# microzed_breakout_v0_6_0b79851d.net
KiCad netlist of a schematic drawn in EAGLE
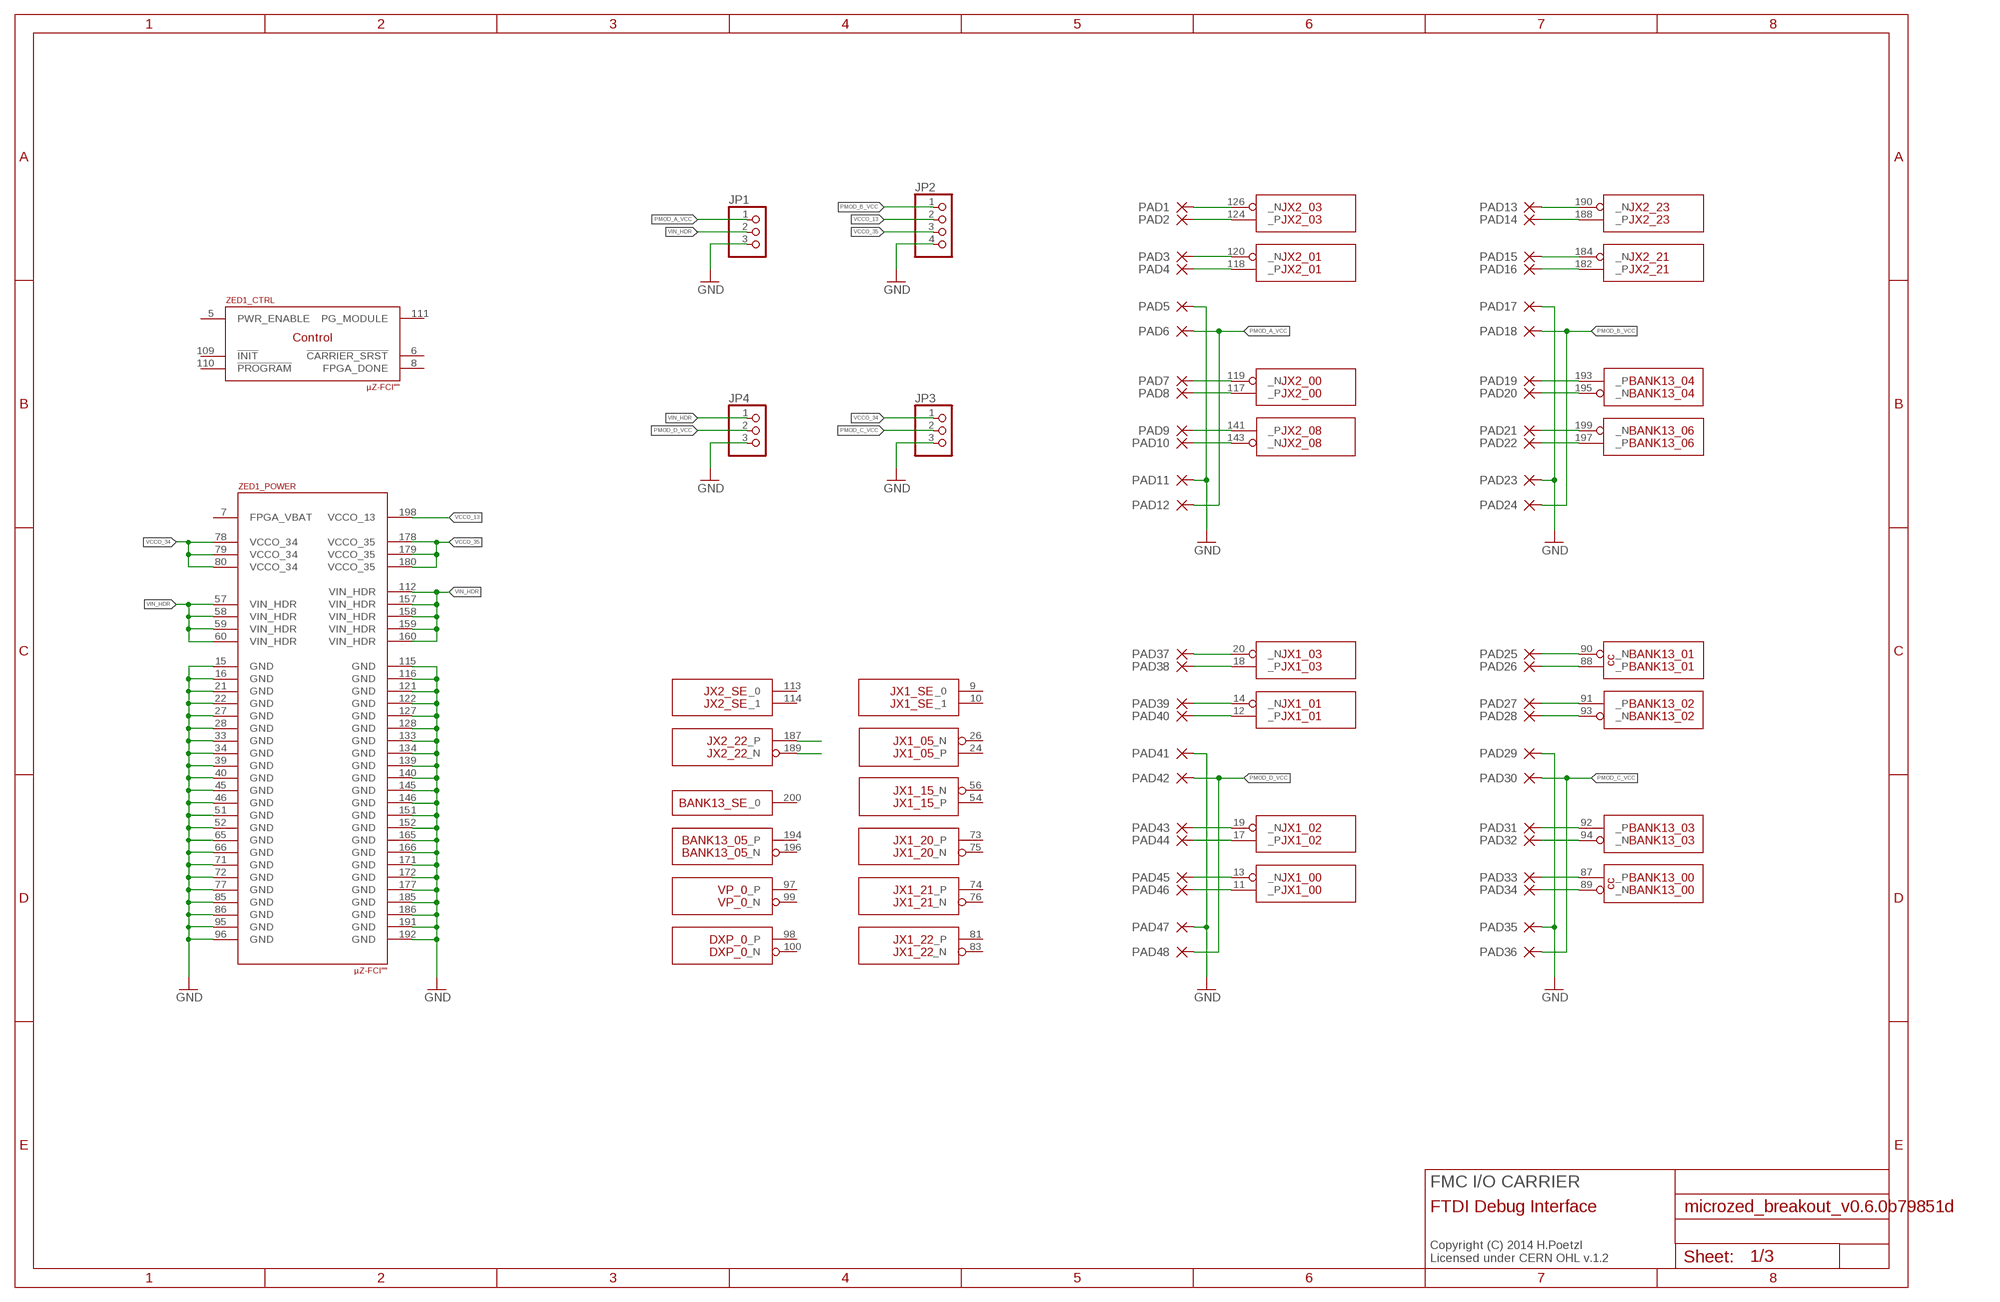
[diagram p0: schematic, sheet 1]
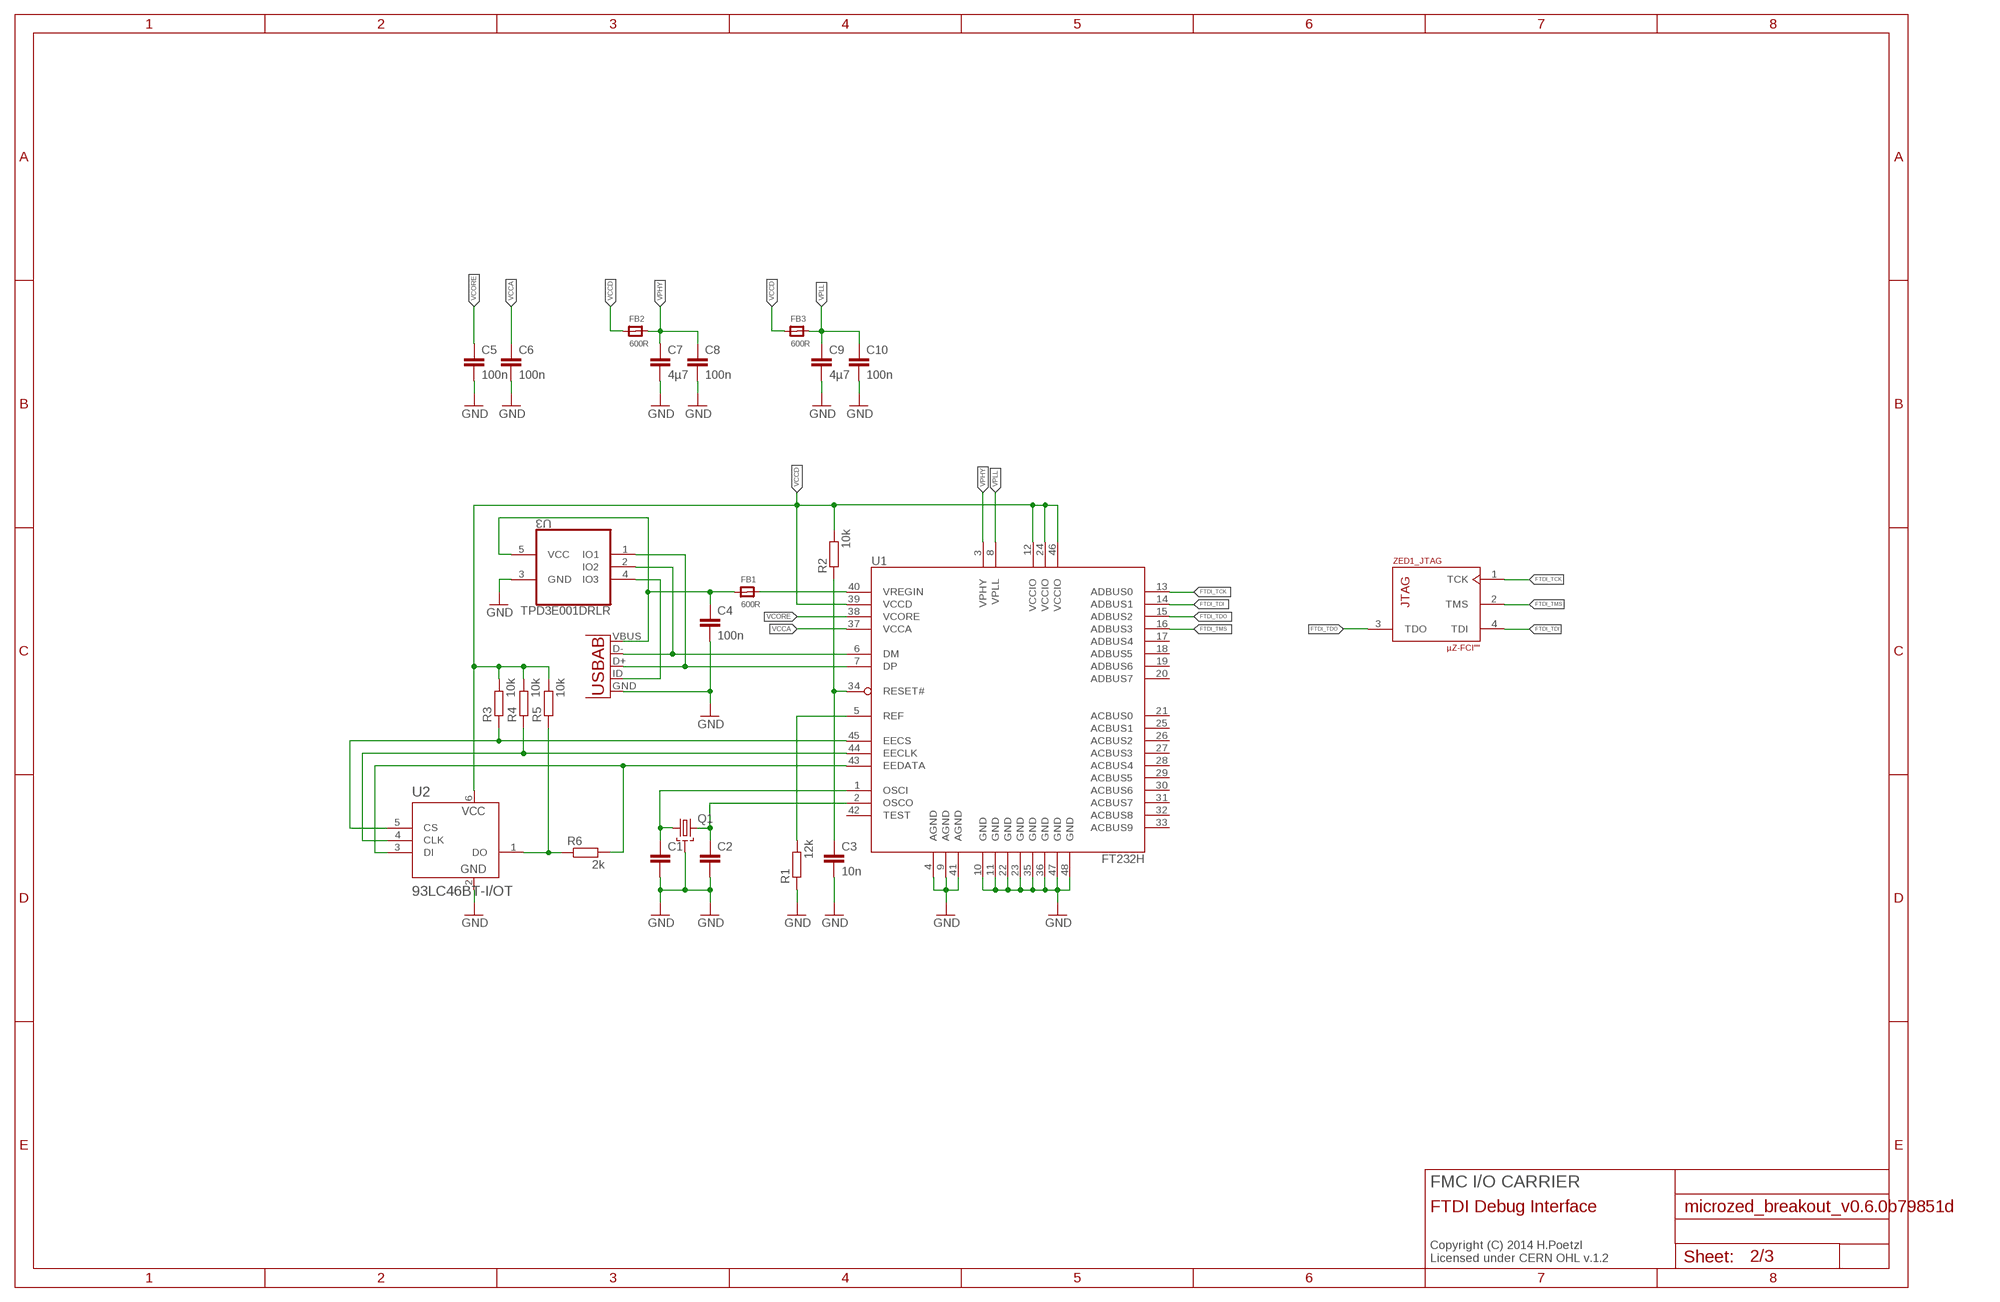
[diagram p1: schematic, sheet 2]
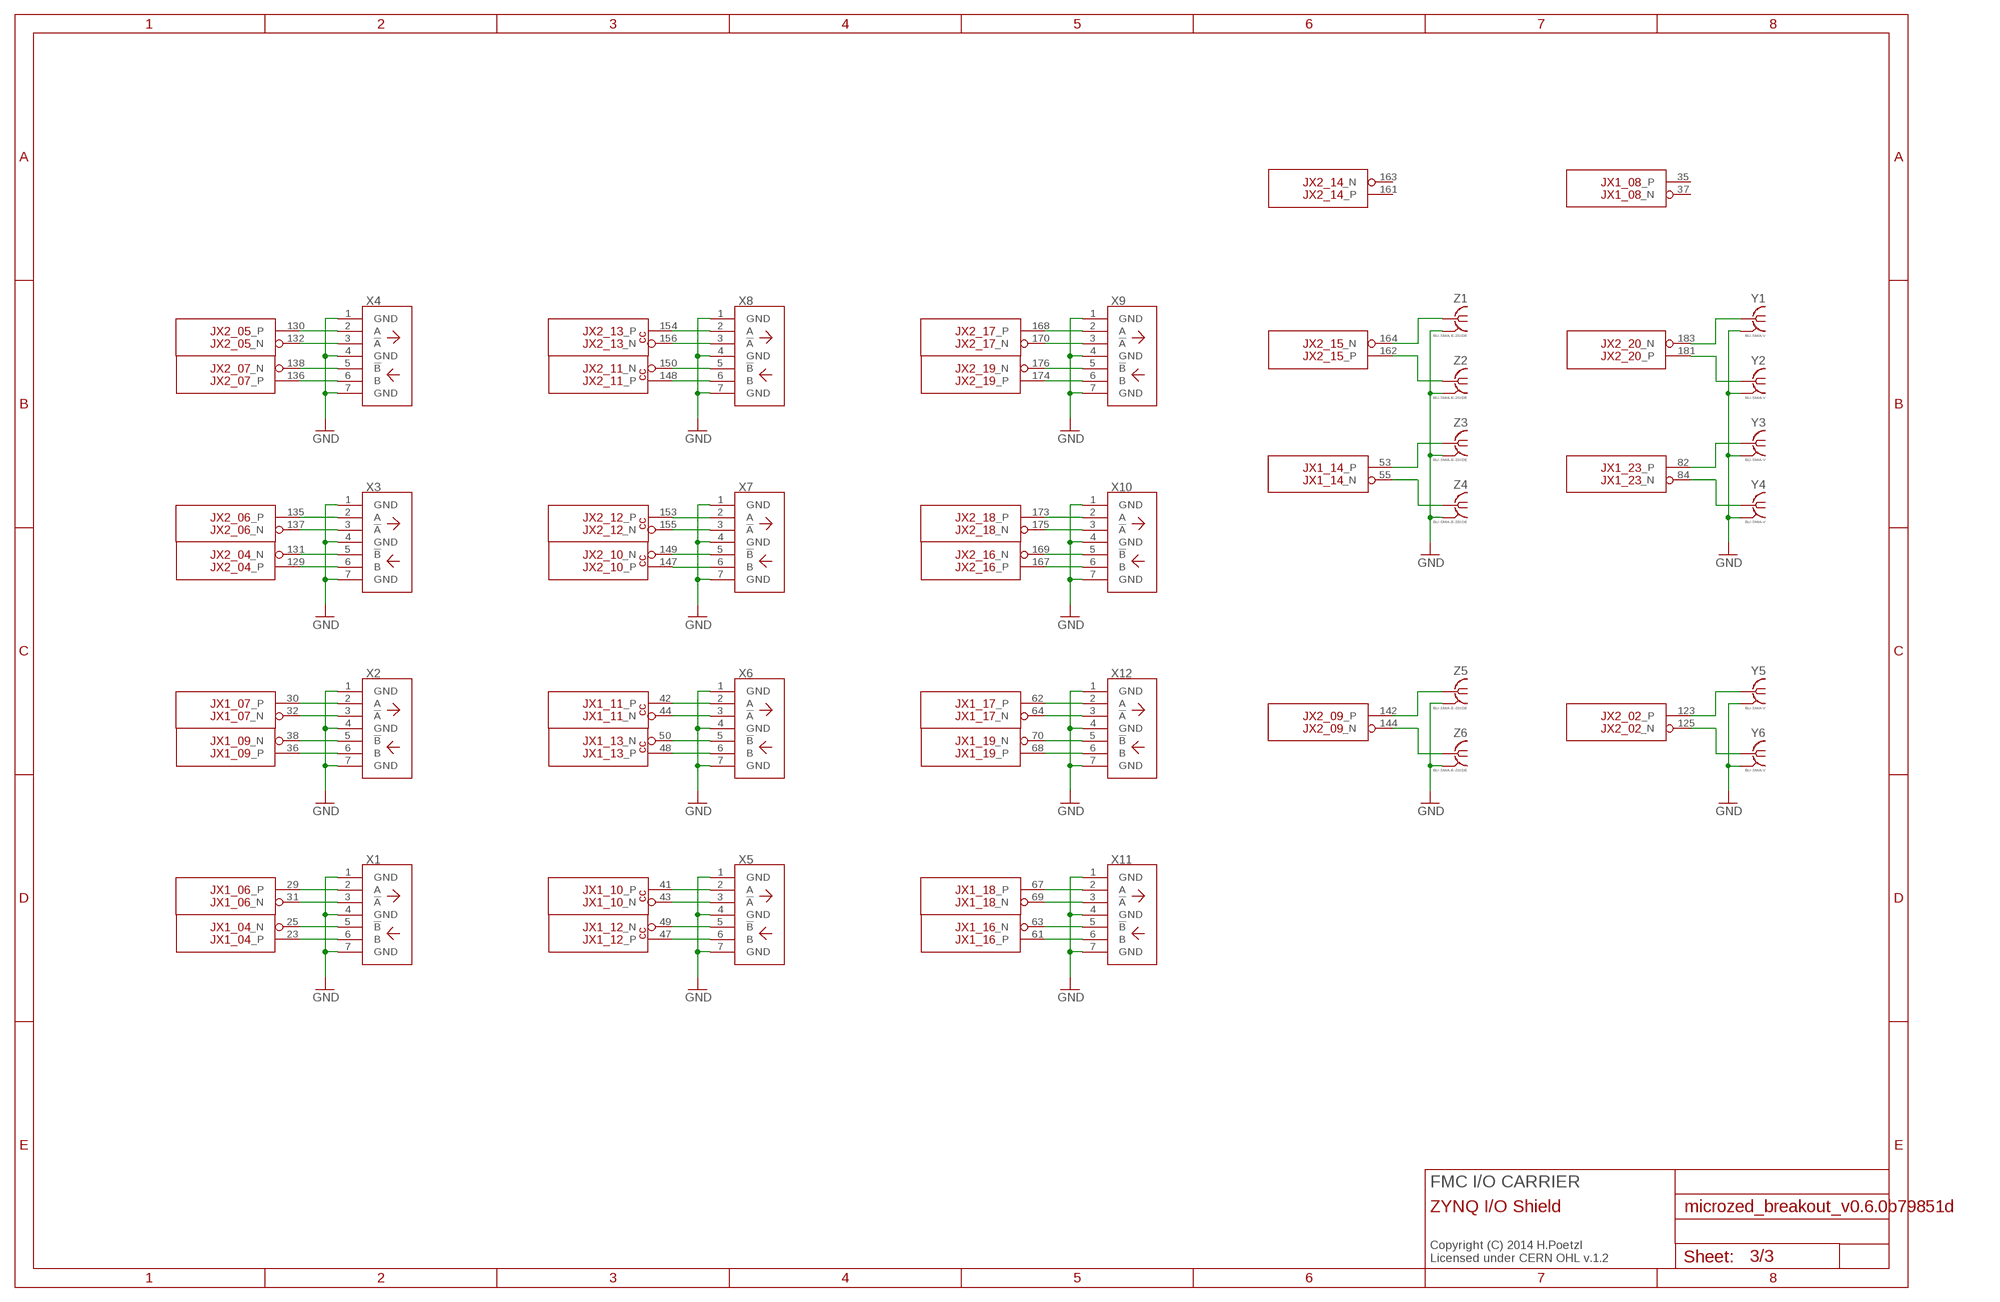
[diagram p2: schematic, sheet 3]

(export (version "E")
  (design (tool "Eeschema 10.0.6"))
  (components
    (comp (ref "C1")
      (value "C-EUC0402K")
      (footprint "eagle-import:C0402K")
      (libsource (lib "eagle-import") (part "C-EUC0402K"))
    )
    (comp (ref "C2")
      (value "C-EUC0402K")
      (footprint "eagle-import:C0402K")
      (libsource (lib "eagle-import") (part "C-EUC0402K"))
    )
    (comp (ref "C3")
      (value "10n")
      (footprint "eagle-import:C0402K")
      (libsource (lib "eagle-import") (part "C-EUC0402K"))
    )
    (comp (ref "C4")
      (value "100n")
      (footprint "eagle-import:C0402K")
      (libsource (lib "eagle-import") (part "C-EUC0402K"))
    )
    (comp (ref "C5")
      (value "100n")
      (footprint "eagle-import:C0402K")
      (libsource (lib "eagle-import") (part "C-EUC0402K"))
    )
    (comp (ref "C6")
      (value "100n")
      (footprint "eagle-import:C0402K")
      (libsource (lib "eagle-import") (part "C-EUC0402K"))
    )
    (comp (ref "C7")
      (value "4µ7")
      (footprint "eagle-import:C0402K")
      (libsource (lib "eagle-import") (part "C-EUC0402K"))
    )
    (comp (ref "C8")
      (value "100n")
      (footprint "eagle-import:C0402K")
      (libsource (lib "eagle-import") (part "C-EUC0402K"))
    )
    (comp (ref "C9")
      (value "4µ7")
      (footprint "eagle-import:C0402K")
      (libsource (lib "eagle-import") (part "C-EUC0402K"))
    )
    (comp (ref "C10")
      (value "100n")
      (footprint "eagle-import:C0402K")
      (libsource (lib "eagle-import") (part "C-EUC0402K"))
    )
    (comp (ref "FB1")
      (value "600R")
      (footprint "eagle-import:_0603MP")
      (libsource (lib "eagle-import") (part "FERRITE_0603MP"))
    )
    (comp (ref "FB2")
      (value "600R")
      (footprint "eagle-import:_0603MP")
      (libsource (lib "eagle-import") (part "FERRITE_0603MP"))
    )
    (comp (ref "FB3")
      (value "600R")
      (footprint "eagle-import:_0603MP")
      (libsource (lib "eagle-import") (part "FERRITE_0603MP"))
    )
    (comp (ref "Q1")
      (value "SMD-4P-2G-3.2X2.5")
      (footprint "eagle-import:ABM8G")
      (libsource (lib "eagle-import") (part "SMD-4P-2G-3.2X2.5"))
    )
    (comp (ref "R1")
      (value "12k")
      (footprint "eagle-import:R0402")
      (libsource (lib "eagle-import") (part "R-EU_R0402"))
    )
    (comp (ref "R2")
      (value "10k")
      (footprint "eagle-import:R0402")
      (libsource (lib "eagle-import") (part "R-EU_R0402"))
    )
    (comp (ref "R3")
      (value "10k")
      (footprint "eagle-import:R0402")
      (libsource (lib "eagle-import") (part "R-EU_R0402"))
    )
    (comp (ref "R4")
      (value "10k")
      (footprint "eagle-import:R0402")
      (libsource (lib "eagle-import") (part "R-EU_R0402"))
    )
    (comp (ref "R5")
      (value "10k")
      (footprint "eagle-import:R0402")
      (libsource (lib "eagle-import") (part "R-EU_R0402"))
    )
    (comp (ref "R6")
      (value "2k")
      (footprint "eagle-import:R0402")
      (libsource (lib "eagle-import") (part "R-EU_R0402"))
    )
    (comp (ref "U1")
      (value "FT232H")
      (footprint "eagle-import:LQFP48")
      (libsource (lib "eagle-import") (part "FT232H"))
    )
    (comp (ref "U2")
      (value "93LC46BT-I/OT")
      (footprint "eagle-import:SOT95P280X145-6N")
      (libsource (lib "eagle-import") (part "93LC46BT-I/OT"))
    )
    (comp (ref "U3")
      (value "TPD3E001DRLR")
      (footprint "eagle-import:SOT50P160X60-5N")
      (libsource (lib "eagle-import") (part "TPD3E001DRLR"))
    )
    (comp (ref "USB")
      (value "USB-AB")
      (footprint "eagle-import:USB-AB-MICRO-SMD")
      (libsource (lib "eagle-import") (part "USB-AB"))
    )
    (comp (ref "ZED1")
      (value "µZ-FCI\"\"")
      (footprint "eagle-import:µZ")
      (libsource (lib "eagle-import") (part "µZ-FCI{dblquote}{dblquote}"))
    )
    (comp (ref "X1")
      (value "SATA7-SMD-VERT")
      (footprint "eagle-import:SATA7-SMD-VERT")
      (libsource (lib "eagle-import") (part "SATA7-SMD-VERT"))
    )
    (comp (ref "X2")
      (value "SATA7-VERT")
      (footprint "eagle-import:SATA7-VERT")
      (libsource (lib "eagle-import") (part "SATA7-VERT"))
    )
    (comp (ref "X3")
      (value "SATA7-VERT")
      (footprint "eagle-import:SATA7-VERT")
      (libsource (lib "eagle-import") (part "SATA7-VERT"))
    )
    (comp (ref "X4")
      (value "SATA7-SMD-VERT")
      (footprint "eagle-import:SATA7-SMD-VERT")
      (libsource (lib "eagle-import") (part "SATA7-SMD-VERT"))
    )
    (comp (ref "X5")
      (value "SATA7-SMD-VERT")
      (footprint "eagle-import:SATA7-SMD-VERT")
      (libsource (lib "eagle-import") (part "SATA7-SMD-VERT"))
    )
    (comp (ref "X6")
      (value "SATA7-VERT")
      (footprint "eagle-import:SATA7-VERT")
      (libsource (lib "eagle-import") (part "SATA7-VERT"))
    )
    (comp (ref "X7")
      (value "SATA7-VERT")
      (footprint "eagle-import:SATA7-VERT")
      (libsource (lib "eagle-import") (part "SATA7-VERT"))
    )
    (comp (ref "X8")
      (value "SATA7-SMD-VERT")
      (footprint "eagle-import:SATA7-SMD-VERT")
      (libsource (lib "eagle-import") (part "SATA7-SMD-VERT"))
    )
    (comp (ref "X9")
      (value "SATA7-SMD-VERT")
      (footprint "eagle-import:SATA7-SMD-VERT")
      (libsource (lib "eagle-import") (part "SATA7-SMD-VERT"))
    )
    (comp (ref "X10")
      (value "SATA7-VERT")
      (footprint "eagle-import:SATA7-VERT")
      (libsource (lib "eagle-import") (part "SATA7-VERT"))
    )
    (comp (ref "X11")
      (value "SATA7-SMD-VERT")
      (footprint "eagle-import:SATA7-SMD-VERT")
      (libsource (lib "eagle-import") (part "SATA7-SMD-VERT"))
    )
    (comp (ref "X12")
      (value "SATA7-VERT")
      (footprint "eagle-import:SATA7-VERT")
      (libsource (lib "eagle-import") (part "SATA7-VERT"))
    )
    (comp (ref "Y1")
      (value "BU-SMA-V")
      (footprint "eagle-import:BU-SMA-V")
      (libsource (lib "eagle-import") (part "BU-SMA-V"))
    )
    (comp (ref "Y2")
      (value "BU-SMA-V")
      (footprint "eagle-import:BU-SMA-V")
      (libsource (lib "eagle-import") (part "BU-SMA-V"))
    )
    (comp (ref "Y3")
      (value "BU-SMA-V")
      (footprint "eagle-import:BU-SMA-V")
      (libsource (lib "eagle-import") (part "BU-SMA-V"))
    )
    (comp (ref "Y4")
      (value "BU-SMA-V")
      (footprint "eagle-import:BU-SMA-V")
      (libsource (lib "eagle-import") (part "BU-SMA-V"))
    )
    (comp (ref "Y5")
      (value "BU-SMA-V")
      (footprint "eagle-import:BU-SMA-V")
      (libsource (lib "eagle-import") (part "BU-SMA-V"))
    )
    (comp (ref "Y6")
      (value "BU-SMA-V")
      (footprint "eagle-import:BU-SMA-V")
      (libsource (lib "eagle-import") (part "BU-SMA-V"))
    )
    (comp (ref "Z1")
      (value "BU-SMA-E-2SIDE")
      (footprint "eagle-import:SMA_EDGE_2SIDE")
      (libsource (lib "eagle-import") (part "BU-SMA-E-2SIDE"))
    )
    (comp (ref "Z2")
      (value "BU-SMA-E-2SIDE")
      (footprint "eagle-import:SMA_EDGE_2SIDE")
      (libsource (lib "eagle-import") (part "BU-SMA-E-2SIDE"))
    )
    (comp (ref "Z3")
      (value "BU-SMA-E-2SIDE")
      (footprint "eagle-import:SMA_EDGE_2SIDE")
      (libsource (lib "eagle-import") (part "BU-SMA-E-2SIDE"))
    )
    (comp (ref "Z4")
      (value "BU-SMA-E-2SIDE")
      (footprint "eagle-import:SMA_EDGE_2SIDE")
      (libsource (lib "eagle-import") (part "BU-SMA-E-2SIDE"))
    )
    (comp (ref "Z5")
      (value "BU-SMA-E-2SIDE")
      (footprint "eagle-import:SMA_EDGE_2SIDE")
      (libsource (lib "eagle-import") (part "BU-SMA-E-2SIDE"))
    )
    (comp (ref "Z6")
      (value "BU-SMA-E-2SIDE")
      (footprint "eagle-import:SMA_EDGE_2SIDE")
      (libsource (lib "eagle-import") (part "BU-SMA-E-2SIDE"))
    )
    (comp (ref "JP1")
      (value "PINHD-1X03_2.54")
      (footprint "eagle-import:1X03")
      (libsource (lib "eagle-import") (part "PINHD-1X03_2.54"))
    )
    (comp (ref "JP2")
      (value "PINHD-1X04_2.54")
      (footprint "eagle-import:1X04")
      (libsource (lib "eagle-import") (part "PINHD-1X04_2.54"))
    )
    (comp (ref "JP3")
      (value "PINHD-1X03_2.54")
      (footprint "eagle-import:1X03")
      (libsource (lib "eagle-import") (part "PINHD-1X03_2.54"))
    )
    (comp (ref "JP4")
      (value "PINHD-1X03_2.54")
      (footprint "eagle-import:1X03")
      (libsource (lib "eagle-import") (part "PINHD-1X03_2.54"))
    )
    (comp (ref "PAD1")
      (value "SMD-PAD1.6X3.8MM-U")
      (footprint "eagle-import:1.6X3.8U-MM")
      (libsource (lib "eagle-import") (part "SMD-PAD1.6X3.8MM-U"))
    )
    (comp (ref "PAD2")
      (value "SMD-PAD1.6X3.8MM-U")
      (footprint "eagle-import:1.6X3.8U-MM")
      (libsource (lib "eagle-import") (part "SMD-PAD1.6X3.8MM-U"))
    )
    (comp (ref "PAD3")
      (value "SMD-PAD1.6X3.8MM-U")
      (footprint "eagle-import:1.6X3.8U-MM")
      (libsource (lib "eagle-import") (part "SMD-PAD1.6X3.8MM-U"))
    )
    (comp (ref "PAD4")
      (value "SMD-PAD1.6X3.8MM-U")
      (footprint "eagle-import:1.6X3.8U-MM")
      (libsource (lib "eagle-import") (part "SMD-PAD1.6X3.8MM-U"))
    )
    (comp (ref "PAD5")
      (value "SMD-PAD1.6X3.8MM-U")
      (footprint "eagle-import:1.6X3.8U-MM")
      (libsource (lib "eagle-import") (part "SMD-PAD1.6X3.8MM-U"))
    )
    (comp (ref "PAD6")
      (value "SMD-PAD1.6X3.8MM-U")
      (footprint "eagle-import:1.6X3.8U-MM")
      (libsource (lib "eagle-import") (part "SMD-PAD1.6X3.8MM-U"))
    )
    (comp (ref "PAD7")
      (value "SMD-PAD1.6X3.8MM-U")
      (footprint "eagle-import:1.6X3.8U-MM")
      (libsource (lib "eagle-import") (part "SMD-PAD1.6X3.8MM-U"))
    )
    (comp (ref "PAD8")
      (value "SMD-PAD1.6X3.8MM-U")
      (footprint "eagle-import:1.6X3.8U-MM")
      (libsource (lib "eagle-import") (part "SMD-PAD1.6X3.8MM-U"))
    )
    (comp (ref "PAD9")
      (value "SMD-PAD1.6X3.8MM-U")
      (footprint "eagle-import:1.6X3.8U-MM")
      (libsource (lib "eagle-import") (part "SMD-PAD1.6X3.8MM-U"))
    )
    (comp (ref "PAD10")
      (value "SMD-PAD1.6X3.8MM-U")
      (footprint "eagle-import:1.6X3.8U-MM")
      (libsource (lib "eagle-import") (part "SMD-PAD1.6X3.8MM-U"))
    )
    (comp (ref "PAD11")
      (value "SMD-PAD1.6X3.8MM-U")
      (footprint "eagle-import:1.6X3.8U-MM")
      (libsource (lib "eagle-import") (part "SMD-PAD1.6X3.8MM-U"))
    )
    (comp (ref "PAD12")
      (value "SMD-PAD1.6X3.8MM-U")
      (footprint "eagle-import:1.6X3.8U-MM")
      (libsource (lib "eagle-import") (part "SMD-PAD1.6X3.8MM-U"))
    )
    (comp (ref "PAD13")
      (value "SMD-PAD1.6X3.8MM-U")
      (footprint "eagle-import:1.6X3.8U-MM")
      (libsource (lib "eagle-import") (part "SMD-PAD1.6X3.8MM-U"))
    )
    (comp (ref "PAD14")
      (value "SMD-PAD1.6X3.8MM-U")
      (footprint "eagle-import:1.6X3.8U-MM")
      (libsource (lib "eagle-import") (part "SMD-PAD1.6X3.8MM-U"))
    )
    (comp (ref "PAD15")
      (value "SMD-PAD1.6X3.8MM-U")
      (footprint "eagle-import:1.6X3.8U-MM")
      (libsource (lib "eagle-import") (part "SMD-PAD1.6X3.8MM-U"))
    )
    (comp (ref "PAD16")
      (value "SMD-PAD1.6X3.8MM-U")
      (footprint "eagle-import:1.6X3.8U-MM")
      (libsource (lib "eagle-import") (part "SMD-PAD1.6X3.8MM-U"))
    )
    (comp (ref "PAD17")
      (value "SMD-PAD1.6X3.8MM-U")
      (footprint "eagle-import:1.6X3.8U-MM")
      (libsource (lib "eagle-import") (part "SMD-PAD1.6X3.8MM-U"))
    )
    (comp (ref "PAD18")
      (value "SMD-PAD1.6X3.8MM-U")
      (footprint "eagle-import:1.6X3.8U-MM")
      (libsource (lib "eagle-import") (part "SMD-PAD1.6X3.8MM-U"))
    )
    (comp (ref "PAD19")
      (value "SMD-PAD1.6X3.8MM-U")
      (footprint "eagle-import:1.6X3.8U-MM")
      (libsource (lib "eagle-import") (part "SMD-PAD1.6X3.8MM-U"))
    )
    (comp (ref "PAD20")
      (value "SMD-PAD1.6X3.8MM-U")
      (footprint "eagle-import:1.6X3.8U-MM")
      (libsource (lib "eagle-import") (part "SMD-PAD1.6X3.8MM-U"))
    )
    (comp (ref "PAD21")
      (value "SMD-PAD1.6X3.8MM-U")
      (footprint "eagle-import:1.6X3.8U-MM")
      (libsource (lib "eagle-import") (part "SMD-PAD1.6X3.8MM-U"))
    )
    (comp (ref "PAD22")
      (value "SMD-PAD1.6X3.8MM-U")
      (footprint "eagle-import:1.6X3.8U-MM")
      (libsource (lib "eagle-import") (part "SMD-PAD1.6X3.8MM-U"))
    )
    (comp (ref "PAD23")
      (value "SMD-PAD1.6X3.8MM-U")
      (footprint "eagle-import:1.6X3.8U-MM")
      (libsource (lib "eagle-import") (part "SMD-PAD1.6X3.8MM-U"))
    )
    (comp (ref "PAD24")
      (value "SMD-PAD1.6X3.8MM-U")
      (footprint "eagle-import:1.6X3.8U-MM")
      (libsource (lib "eagle-import") (part "SMD-PAD1.6X3.8MM-U"))
    )
    (comp (ref "PAD25")
      (value "SMD-PAD1.6X3.8MM-U")
      (footprint "eagle-import:1.6X3.8U-MM")
      (libsource (lib "eagle-import") (part "SMD-PAD1.6X3.8MM-U"))
    )
    (comp (ref "PAD26")
      (value "SMD-PAD1.6X3.8MM-U")
      (footprint "eagle-import:1.6X3.8U-MM")
      (libsource (lib "eagle-import") (part "SMD-PAD1.6X3.8MM-U"))
    )
    (comp (ref "PAD27")
      (value "SMD-PAD1.6X3.8MM-U")
      (footprint "eagle-import:1.6X3.8U-MM")
      (libsource (lib "eagle-import") (part "SMD-PAD1.6X3.8MM-U"))
    )
    (comp (ref "PAD28")
      (value "SMD-PAD1.6X3.8MM-U")
      (footprint "eagle-import:1.6X3.8U-MM")
      (libsource (lib "eagle-import") (part "SMD-PAD1.6X3.8MM-U"))
    )
    (comp (ref "PAD29")
      (value "SMD-PAD1.6X3.8MM-U")
      (footprint "eagle-import:1.6X3.8U-MM")
      (libsource (lib "eagle-import") (part "SMD-PAD1.6X3.8MM-U"))
    )
    (comp (ref "PAD30")
      (value "SMD-PAD1.6X3.8MM-U")
      (footprint "eagle-import:1.6X3.8U-MM")
      (libsource (lib "eagle-import") (part "SMD-PAD1.6X3.8MM-U"))
    )
    (comp (ref "PAD31")
      (value "SMD-PAD1.6X3.8MM-U")
      (footprint "eagle-import:1.6X3.8U-MM")
      (libsource (lib "eagle-import") (part "SMD-PAD1.6X3.8MM-U"))
    )
    (comp (ref "PAD32")
      (value "SMD-PAD1.6X3.8MM-U")
      (footprint "eagle-import:1.6X3.8U-MM")
      (libsource (lib "eagle-import") (part "SMD-PAD1.6X3.8MM-U"))
    )
    (comp (ref "PAD33")
      (value "SMD-PAD1.6X3.8MM-U")
      (footprint "eagle-import:1.6X3.8U-MM")
      (libsource (lib "eagle-import") (part "SMD-PAD1.6X3.8MM-U"))
    )
    (comp (ref "PAD34")
      (value "SMD-PAD1.6X3.8MM-U")
      (footprint "eagle-import:1.6X3.8U-MM")
      (libsource (lib "eagle-import") (part "SMD-PAD1.6X3.8MM-U"))
    )
    (comp (ref "PAD35")
      (value "SMD-PAD1.6X3.8MM-U")
      (footprint "eagle-import:1.6X3.8U-MM")
      (libsource (lib "eagle-import") (part "SMD-PAD1.6X3.8MM-U"))
    )
    (comp (ref "PAD36")
      (value "SMD-PAD1.6X3.8MM-U")
      (footprint "eagle-import:1.6X3.8U-MM")
      (libsource (lib "eagle-import") (part "SMD-PAD1.6X3.8MM-U"))
    )
    (comp (ref "PAD37")
      (value "SMD-PAD1.6X3.8MM-U")
      (footprint "eagle-import:1.6X3.8U-MM")
      (libsource (lib "eagle-import") (part "SMD-PAD1.6X3.8MM-U"))
    )
    (comp (ref "PAD38")
      (value "SMD-PAD1.6X3.8MM-U")
      (footprint "eagle-import:1.6X3.8U-MM")
      (libsource (lib "eagle-import") (part "SMD-PAD1.6X3.8MM-U"))
    )
    (comp (ref "PAD39")
      (value "SMD-PAD1.6X3.8MM-U")
      (footprint "eagle-import:1.6X3.8U-MM")
      (libsource (lib "eagle-import") (part "SMD-PAD1.6X3.8MM-U"))
    )
    (comp (ref "PAD40")
      (value "SMD-PAD1.6X3.8MM-U")
      (footprint "eagle-import:1.6X3.8U-MM")
      (libsource (lib "eagle-import") (part "SMD-PAD1.6X3.8MM-U"))
    )
    (comp (ref "PAD41")
      (value "SMD-PAD1.6X3.8MM-U")
      (footprint "eagle-import:1.6X3.8U-MM")
      (libsource (lib "eagle-import") (part "SMD-PAD1.6X3.8MM-U"))
    )
    (comp (ref "PAD42")
      (value "SMD-PAD1.6X3.8MM-U")
      (footprint "eagle-import:1.6X3.8U-MM")
      (libsource (lib "eagle-import") (part "SMD-PAD1.6X3.8MM-U"))
    )
    (comp (ref "PAD43")
      (value "SMD-PAD1.6X3.8MM-U")
      (footprint "eagle-import:1.6X3.8U-MM")
      (libsource (lib "eagle-import") (part "SMD-PAD1.6X3.8MM-U"))
    )
    (comp (ref "PAD44")
      (value "SMD-PAD1.6X3.8MM-U")
      (footprint "eagle-import:1.6X3.8U-MM")
      (libsource (lib "eagle-import") (part "SMD-PAD1.6X3.8MM-U"))
    )
    (comp (ref "PAD45")
      (value "SMD-PAD1.6X3.8MM-U")
      (footprint "eagle-import:1.6X3.8U-MM")
      (libsource (lib "eagle-import") (part "SMD-PAD1.6X3.8MM-U"))
    )
    (comp (ref "PAD46")
      (value "SMD-PAD1.6X3.8MM-U")
      (footprint "eagle-import:1.6X3.8U-MM")
      (libsource (lib "eagle-import") (part "SMD-PAD1.6X3.8MM-U"))
    )
    (comp (ref "PAD47")
      (value "SMD-PAD1.6X3.8MM-U")
      (footprint "eagle-import:1.6X3.8U-MM")
      (libsource (lib "eagle-import") (part "SMD-PAD1.6X3.8MM-U"))
    )
    (comp (ref "PAD48")
      (value "SMD-PAD1.6X3.8MM-U")
      (footprint "eagle-import:1.6X3.8U-MM")
      (libsource (lib "eagle-import") (part "SMD-PAD1.6X3.8MM-U"))
    )
  )
  (nets
    (net (code "1") (name "FPGA_VBAT") (class "Default")
      (node (ref "ZED1") (pin "7") (pinfunction "FPGA_VBAT_7") (pintype "power_in"))
    )
    (net (code "2") (name "FTDI_TCK") (class "Default")
      (node (ref "U1") (pin "13") (pinfunction "ADBUS0_13") (pintype "output"))
      (node (ref "ZED1") (pin "1") (pinfunction "TCK_1") (pintype "output"))
    )
    (net (code "3") (name "FTDI_TDI") (class "Default")
      (node (ref "U1") (pin "14") (pinfunction "ADBUS1_14") (pintype "input"))
      (node (ref "ZED1") (pin "4") (pinfunction "TDI_4") (pintype "output"))
    )
    (net (code "4") (name "FTDI_TDO") (class "Default")
      (node (ref "U1") (pin "15") (pinfunction "ADBUS2_15") (pintype "output"))
      (node (ref "ZED1") (pin "3") (pinfunction "TDO_3") (pintype "input"))
    )
    (net (code "5") (name "FTDI_TMS") (class "Default")
      (node (ref "U1") (pin "16") (pinfunction "ADBUS3_16") (pintype "input"))
      (node (ref "ZED1") (pin "2") (pinfunction "TMS_2") (pintype "output"))
    )
    (net (code "6") (name "GND") (class "Default")
      (node (ref "C1") (pin "2") (pinfunction "2_2") (pintype "passive"))
      (node (ref "C10") (pin "2") (pinfunction "2_2") (pintype "passive"))
      (node (ref "C2") (pin "2") (pinfunction "2_2") (pintype "passive"))
      (node (ref "C3") (pin "2") (pinfunction "2_2") (pintype "passive"))
      (node (ref "C4") (pin "2") (pinfunction "2_2") (pintype "passive"))
      (node (ref "C5") (pin "2") (pinfunction "2_2") (pintype "passive"))
      (node (ref "C6") (pin "2") (pinfunction "2_2") (pintype "passive"))
      (node (ref "C7") (pin "2") (pinfunction "2_2") (pintype "passive"))
      (node (ref "C8") (pin "2") (pinfunction "2_2") (pintype "passive"))
      (node (ref "C9") (pin "2") (pinfunction "2_2") (pintype "passive"))
      (node (ref "JP1") (pin "3") (pinfunction "3_3") (pintype "passive"))
      (node (ref "JP2") (pin "4") (pinfunction "4_4") (pintype "passive"))
      (node (ref "JP3") (pin "3") (pinfunction "3_3") (pintype "passive"))
      (node (ref "JP4") (pin "3") (pinfunction "3_3") (pintype "passive"))
      (node (ref "PAD11") (pin "1") (pinfunction "P_1") (pintype "passive"))
      (node (ref "PAD17") (pin "1") (pinfunction "P_1") (pintype "passive"))
      (node (ref "PAD23") (pin "1") (pinfunction "P_1") (pintype "passive"))
      (node (ref "PAD29") (pin "1") (pinfunction "P_1") (pintype "passive"))
      (node (ref "PAD35") (pin "1") (pinfunction "P_1") (pintype "passive"))
      (node (ref "PAD41") (pin "1") (pinfunction "P_1") (pintype "passive"))
      (node (ref "PAD47") (pin "1") (pinfunction "P_1") (pintype "passive"))
      (node (ref "PAD5") (pin "1") (pinfunction "P_1") (pintype "passive"))
      (node (ref "Q1") (pin "2") (pinfunction "GND_2") (pintype "power_in"))
      (node (ref "Q1") (pin "4") (pinfunction "GND_4") (pintype "power_in"))
      (node (ref "R1") (pin "1") (pinfunction "1_1") (pintype "passive"))
      (node (ref "U1") (pin "10") (pinfunction "GND_10") (pintype "power_in"))
      (node (ref "U1") (pin "11") (pinfunction "GND_11") (pintype "power_in"))
      (node (ref "U1") (pin "22") (pinfunction "GND_22") (pintype "power_in"))
      (node (ref "U1") (pin "23") (pinfunction "GND_23") (pintype "power_in"))
      (node (ref "U1") (pin "35") (pinfunction "GND_35") (pintype "power_in"))
      (node (ref "U1") (pin "36") (pinfunction "GND_36") (pintype "power_in"))
      (node (ref "U1") (pin "4") (pinfunction "AGND_4") (pintype "power_in"))
      (node (ref "U1") (pin "41") (pinfunction "AGND_41") (pintype "power_in"))
      (node (ref "U1") (pin "47") (pinfunction "GND_47") (pintype "power_in"))
      (node (ref "U1") (pin "48") (pinfunction "GND_48") (pintype "power_in"))
      (node (ref "U1") (pin "9") (pinfunction "AGND_9") (pintype "power_in"))
      (node (ref "U2") (pin "2") (pinfunction "VSS_2") (pintype "power_in"))
      (node (ref "U3") (pin "3") (pinfunction "GND_3") (pintype "passive"))
      (node (ref "USB") (pin "GND") (pinfunction "GND_GND") (pintype "bidirectional"))
      (node (ref "X1") (pin "1") (pinfunction "GND_1") (pintype "passive"))
      (node (ref "X1") (pin "4") (pinfunction "GND_4") (pintype "passive"))
      (node (ref "X1") (pin "7") (pinfunction "GND_7") (pintype "passive"))
      (node (ref "X10") (pin "1") (pinfunction "GND_1") (pintype "passive"))
      (node (ref "X10") (pin "4") (pinfunction "GND_4") (pintype "passive"))
      (node (ref "X10") (pin "7") (pinfunction "GND_7") (pintype "passive"))
      (node (ref "X11") (pin "1") (pinfunction "GND_1") (pintype "passive"))
      (node (ref "X11") (pin "4") (pinfunction "GND_4") (pintype "passive"))
      (node (ref "X11") (pin "7") (pinfunction "GND_7") (pintype "passive"))
      (node (ref "X12") (pin "1") (pinfunction "GND_1") (pintype "passive"))
      (node (ref "X12") (pin "4") (pinfunction "GND_4") (pintype "passive"))
      (node (ref "X12") (pin "7") (pinfunction "GND_7") (pintype "passive"))
      (node (ref "X2") (pin "1") (pinfunction "GND_1") (pintype "passive"))
      (node (ref "X2") (pin "4") (pinfunction "GND_4") (pintype "passive"))
      (node (ref "X2") (pin "7") (pinfunction "GND_7") (pintype "passive"))
      (node (ref "X3") (pin "1") (pinfunction "GND_1") (pintype "passive"))
      (node (ref "X3") (pin "4") (pinfunction "GND_4") (pintype "passive"))
      (node (ref "X3") (pin "7") (pinfunction "GND_7") (pintype "passive"))
      (node (ref "X4") (pin "1") (pinfunction "GND_1") (pintype "passive"))
      (node (ref "X4") (pin "4") (pinfunction "GND_4") (pintype "passive"))
      (node (ref "X4") (pin "7") (pinfunction "GND_7") (pintype "passive"))
      (node (ref "X5") (pin "1") (pinfunction "GND_1") (pintype "passive"))
      (node (ref "X5") (pin "4") (pinfunction "GND_4") (pintype "passive"))
      (node (ref "X5") (pin "7") (pinfunction "GND_7") (pintype "passive"))
      (node (ref "X6") (pin "1") (pinfunction "GND_1") (pintype "passive"))
      (node (ref "X6") (pin "4") (pinfunction "GND_4") (pintype "passive"))
      (node (ref "X6") (pin "7") (pinfunction "GND_7") (pintype "passive"))
      (node (ref "X7") (pin "1") (pinfunction "GND_1") (pintype "passive"))
      (node (ref "X7") (pin "4") (pinfunction "GND_4") (pintype "passive"))
      (node (ref "X7") (pin "7") (pinfunction "GND_7") (pintype "passive"))
      (node (ref "X8") (pin "1") (pinfunction "GND_1") (pintype "passive"))
      (node (ref "X8") (pin "4") (pinfunction "GND_4") (pintype "passive"))
      (node (ref "X8") (pin "7") (pinfunction "GND_7") (pintype "passive"))
      (node (ref "X9") (pin "1") (pinfunction "GND_1") (pintype "passive"))
      (node (ref "X9") (pin "4") (pinfunction "GND_4") (pintype "passive"))
      (node (ref "X9") (pin "7") (pinfunction "GND_7") (pintype "passive"))
      (node (ref "Y1") (pin "2") (pinfunction "2_2") (pintype "passive"))
      (node (ref "Y1") (pin "3") (pinfunction "2_3") (pintype "passive"))
      (node (ref "Y1") (pin "4") (pinfunction "2_4") (pintype "passive"))
      (node (ref "Y1") (pin "5") (pinfunction "2_5") (pintype "passive"))
      (node (ref "Y2") (pin "2") (pinfunction "2_2") (pintype "passive"))
      (node (ref "Y2") (pin "3") (pinfunction "2_3") (pintype "passive"))
      (node (ref "Y2") (pin "4") (pinfunction "2_4") (pintype "passive"))
      (node (ref "Y2") (pin "5") (pinfunction "2_5") (pintype "passive"))
      (node (ref "Y3") (pin "2") (pinfunction "2_2") (pintype "passive"))
      (node (ref "Y3") (pin "3") (pinfunction "2_3") (pintype "passive"))
      (node (ref "Y3") (pin "4") (pinfunction "2_4") (pintype "passive"))
      (node (ref "Y3") (pin "5") (pinfunction "2_5") (pintype "passive"))
      (node (ref "Y4") (pin "2") (pinfunction "2_2") (pintype "passive"))
      (node (ref "Y4") (pin "3") (pinfunction "2_3") (pintype "passive"))
      (node (ref "Y4") (pin "4") (pinfunction "2_4") (pintype "passive"))
      (node (ref "Y4") (pin "5") (pinfunction "2_5") (pintype "passive"))
      (node (ref "Y5") (pin "2") (pinfunction "2_2") (pintype "passive"))
      (node (ref "Y5") (pin "3") (pinfunction "2_3") (pintype "passive"))
      (node (ref "Y5") (pin "4") (pinfunction "2_4") (pintype "passive"))
      (node (ref "Y5") (pin "5") (pinfunction "2_5") (pintype "passive"))
      (node (ref "Y6") (pin "2") (pinfunction "2_2") (pintype "passive"))
      (node (ref "Y6") (pin "3") (pinfunction "2_3") (pintype "passive"))
      (node (ref "Y6") (pin "4") (pinfunction "2_4") (pintype "passive"))
      (node (ref "Y6") (pin "5") (pinfunction "2_5") (pintype "passive"))
      (node (ref "Z1") (pin "2@1") (pinfunction "2_2@1") (pintype "passive"))
      (node (ref "Z1") (pin "2@2") (pinfunction "2_2@2") (pintype "passive"))
      (node (ref "Z1") (pin "2@3") (pinfunction "2_2@3") (pintype "passive"))
      (node (ref "Z1") (pin "2@4") (pinfunction "2_2@4") (pintype "passive"))
      (node (ref "Z2") (pin "2@1") (pinfunction "2_2@1") (pintype "passive"))
      (node (ref "Z2") (pin "2@2") (pinfunction "2_2@2") (pintype "passive"))
      (node (ref "Z2") (pin "2@3") (pinfunction "2_2@3") (pintype "passive"))
      (node (ref "Z2") (pin "2@4") (pinfunction "2_2@4") (pintype "passive"))
      (node (ref "Z3") (pin "2@1") (pinfunction "2_2@1") (pintype "passive"))
      (node (ref "Z3") (pin "2@2") (pinfunction "2_2@2") (pintype "passive"))
      (node (ref "Z3") (pin "2@3") (pinfunction "2_2@3") (pintype "passive"))
      (node (ref "Z3") (pin "2@4") (pinfunction "2_2@4") (pintype "passive"))
      (node (ref "Z4") (pin "2@1") (pinfunction "2_2@1") (pintype "passive"))
      (node (ref "Z4") (pin "2@2") (pinfunction "2_2@2") (pintype "passive"))
      (node (ref "Z4") (pin "2@3") (pinfunction "2_2@3") (pintype "passive"))
      (node (ref "Z4") (pin "2@4") (pinfunction "2_2@4") (pintype "passive"))
      (node (ref "Z5") (pin "2@1") (pinfunction "2_2@1") (pintype "passive"))
      (node (ref "Z5") (pin "2@2") (pinfunction "2_2@2") (pintype "passive"))
      (node (ref "Z5") (pin "2@3") (pinfunction "2_2@3") (pintype "passive"))
      (node (ref "Z5") (pin "2@4") (pinfunction "2_2@4") (pintype "passive"))
      (node (ref "Z6") (pin "2@1") (pinfunction "2_2@1") (pintype "passive"))
      (node (ref "Z6") (pin "2@2") (pinfunction "2_2@2") (pintype "passive"))
      (node (ref "Z6") (pin "2@3") (pinfunction "2_2@3") (pintype "passive"))
      (node (ref "Z6") (pin "2@4") (pinfunction "2_2@4") (pintype "passive"))
      (node (ref "ZED1") (pin "115") (pinfunction "GND_115") (pintype "power_in"))
      (node (ref "ZED1") (pin "116") (pinfunction "GND_116") (pintype "power_in"))
      (node (ref "ZED1") (pin "121") (pinfunction "GND_121") (pintype "power_in"))
      (node (ref "ZED1") (pin "122") (pinfunction "GND_122") (pintype "power_in"))
      (node (ref "ZED1") (pin "127") (pinfunction "GND_127") (pintype "power_in"))
      (node (ref "ZED1") (pin "128") (pinfunction "GND_128") (pintype "power_in"))
      (node (ref "ZED1") (pin "133") (pinfunction "GND_133") (pintype "power_in"))
      (node (ref "ZED1") (pin "134") (pinfunction "GND_134") (pintype "power_in"))
      (node (ref "ZED1") (pin "139") (pinfunction "GND_139") (pintype "power_in"))
      (node (ref "ZED1") (pin "140") (pinfunction "GND_140") (pintype "power_in"))
      (node (ref "ZED1") (pin "145") (pinfunction "GND_145") (pintype "power_in"))
      (node (ref "ZED1") (pin "146") (pinfunction "GND_146") (pintype "power_in"))
      (node (ref "ZED1") (pin "15") (pinfunction "GND_15") (pintype "power_in"))
      (node (ref "ZED1") (pin "151") (pinfunction "GND_151") (pintype "power_in"))
      (node (ref "ZED1") (pin "152") (pinfunction "GND_152") (pintype "power_in"))
      (node (ref "ZED1") (pin "16") (pinfunction "GND_16") (pintype "power_in"))
      (node (ref "ZED1") (pin "165") (pinfunction "GND_165") (pintype "power_in"))
      (node (ref "ZED1") (pin "166") (pinfunction "GND_166") (pintype "power_in"))
      (node (ref "ZED1") (pin "171") (pinfunction "GND_171") (pintype "power_in"))
      (node (ref "ZED1") (pin "172") (pinfunction "GND_172") (pintype "power_in"))
      (node (ref "ZED1") (pin "177") (pinfunction "GND_177") (pintype "power_in"))
      (node (ref "ZED1") (pin "185") (pinfunction "GND_185") (pintype "power_in"))
      (node (ref "ZED1") (pin "186") (pinfunction "GND_186") (pintype "power_in"))
      (node (ref "ZED1") (pin "191") (pinfunction "GND_191") (pintype "power_in"))
      (node (ref "ZED1") (pin "192") (pinfunction "GND_192") (pintype "power_in"))
      (node (ref "ZED1") (pin "21") (pinfunction "GND_21") (pintype "power_in"))
      (node (ref "ZED1") (pin "22") (pinfunction "GND_22") (pintype "power_in"))
      (node (ref "ZED1") (pin "27") (pinfunction "GND_27") (pintype "power_in"))
      (node (ref "ZED1") (pin "28") (pinfunction "GND_28") (pintype "power_in"))
      (node (ref "ZED1") (pin "33") (pinfunction "GND_33") (pintype "power_in"))
      (node (ref "ZED1") (pin "34") (pinfunction "GND_34") (pintype "power_in"))
      (node (ref "ZED1") (pin "39") (pinfunction "GND_39") (pintype "power_in"))
      (node (ref "ZED1") (pin "40") (pinfunction "GND_40") (pintype "power_in"))
      (node (ref "ZED1") (pin "45") (pinfunction "GND_45") (pintype "power_in"))
      (node (ref "ZED1") (pin "46") (pinfunction "GND_46") (pintype "power_in"))
      (node (ref "ZED1") (pin "51") (pinfunction "GND_51") (pintype "power_in"))
      (node (ref "ZED1") (pin "52") (pinfunction "GND_52") (pintype "power_in"))
      (node (ref "ZED1") (pin "65") (pinfunction "GND_65") (pintype "power_in"))
      (node (ref "ZED1") (pin "66") (pinfunction "GND_66") (pintype "power_in"))
      (node (ref "ZED1") (pin "71") (pinfunction "GND_71") (pintype "power_in"))
      (node (ref "ZED1") (pin "72") (pinfunction "GND_72") (pintype "power_in"))
      (node (ref "ZED1") (pin "77") (pinfunction "GND_77") (pintype "power_in"))
      (node (ref "ZED1") (pin "85") (pinfunction "GND_85") (pintype "power_in"))
      (node (ref "ZED1") (pin "86") (pinfunction "GND_86") (pintype "power_in"))
      (node (ref "ZED1") (pin "95") (pinfunction "GND_95") (pintype "power_in"))
      (node (ref "ZED1") (pin "96") (pinfunction "GND_96") (pintype "power_in"))
    )
    (net (code "7") (name "Net-(FB1-P$1)") (class "Default")
      (node (ref "C4") (pin "1") (pinfunction "1_1") (pintype "passive"))
      (node (ref "FB1") (pin "1") (pinfunction "P$1_1") (pintype "passive"))
      (node (ref "U3") (pin "5") (pinfunction "VCC_5") (pintype "power_in"))
      (node (ref "USB") (pin "VBUS") (pinfunction "VBUS_VBUS") (pintype "bidirectional"))
    )
    (net (code "8") (name "Net-(FB1-P$2)") (class "Default")
      (node (ref "FB1") (pin "2") (pinfunction "P$2_2") (pintype "passive"))
      (node (ref "U1") (pin "40") (pinfunction "VREGIN_40") (pintype "power_in"))
    )
    (net (code "9") (name "Net-(PAD1-P)") (class "Default")
      (node (ref "PAD1") (pin "1") (pinfunction "P_1") (pintype "passive"))
      (node (ref "ZED1") (pin "126") (pinfunction "_N_126") (pintype "bidirectional"))
    )
    (net (code "10") (name "Net-(PAD2-P)") (class "Default")
      (node (ref "PAD2") (pin "1") (pinfunction "P_1") (pintype "passive"))
      (node (ref "ZED1") (pin "124") (pinfunction "_P_124") (pintype "bidirectional"))
    )
    (net (code "11") (name "Net-(PAD3-P)") (class "Default")
      (node (ref "PAD3") (pin "1") (pinfunction "P_1") (pintype "passive"))
      (node (ref "ZED1") (pin "120") (pinfunction "_N_120") (pintype "bidirectional"))
    )
    (net (code "12") (name "Net-(PAD4-P)") (class "Default")
      (node (ref "PAD4") (pin "1") (pinfunction "P_1") (pintype "passive"))
      (node (ref "ZED1") (pin "118") (pinfunction "_P_118") (pintype "bidirectional"))
    )
    (net (code "13") (name "Net-(PAD7-P)") (class "Default")
      (node (ref "PAD7") (pin "1") (pinfunction "P_1") (pintype "passive"))
      (node (ref "ZED1") (pin "119") (pinfunction "_N_119") (pintype "bidirectional"))
    )
    (net (code "14") (name "Net-(PAD8-P)") (class "Default")
      (node (ref "PAD8") (pin "1") (pinfunction "P_1") (pintype "passive"))
      (node (ref "ZED1") (pin "117") (pinfunction "_P_117") (pintype "bidirectional"))
    )
    (net (code "15") (name "Net-(PAD9-P)") (class "Default")
      (node (ref "PAD9") (pin "1") (pinfunction "P_1") (pintype "passive"))
      (node (ref "ZED1") (pin "141") (pinfunction "_P_141") (pintype "bidirectional"))
    )
    (net (code "16") (name "Net-(PAD10-P)") (class "Default")
      (node (ref "PAD10") (pin "1") (pinfunction "P_1") (pintype "passive"))
      (node (ref "ZED1") (pin "143") (pinfunction "_N_143") (pintype "bidirectional"))
    )
    (net (code "17") (name "Net-(PAD13-P)") (class "Default")
      (node (ref "PAD13") (pin "1") (pinfunction "P_1") (pintype "passive"))
      (node (ref "ZED1") (pin "190") (pinfunction "_N_190") (pintype "bidirectional"))
    )
    (net (code "18") (name "Net-(PAD14-P)") (class "Default")
      (node (ref "PAD14") (pin "1") (pinfunction "P_1") (pintype "passive"))
      (node (ref "ZED1") (pin "188") (pinfunction "_P_188") (pintype "bidirectional"))
    )
    (net (code "19") (name "Net-(PAD15-P)") (class "Default")
      (node (ref "PAD15") (pin "1") (pinfunction "P_1") (pintype "passive"))
      (node (ref "ZED1") (pin "184") (pinfunction "_N_184") (pintype "bidirectional"))
    )
    (net (code "20") (name "Net-(PAD16-P)") (class "Default")
      (node (ref "PAD16") (pin "1") (pinfunction "P_1") (pintype "passive"))
      (node (ref "ZED1") (pin "182") (pinfunction "_P_182") (pintype "bidirectional"))
    )
    (net (code "21") (name "Net-(PAD19-P)") (class "Default")
      (node (ref "PAD19") (pin "1") (pinfunction "P_1") (pintype "passive"))
      (node (ref "ZED1") (pin "193") (pinfunction "_P_193") (pintype "bidirectional"))
    )
    (net (code "22") (name "Net-(PAD20-P)") (class "Default")
      (node (ref "PAD20") (pin "1") (pinfunction "P_1") (pintype "passive"))
      (node (ref "ZED1") (pin "195") (pinfunction "_N_195") (pintype "bidirectional"))
    )
    (net (code "23") (name "Net-(PAD21-P)") (class "Default")
      (node (ref "PAD21") (pin "1") (pinfunction "P_1") (pintype "passive"))
      (node (ref "ZED1") (pin "199") (pinfunction "_N_199") (pintype "bidirectional"))
    )
    (net (code "24") (name "Net-(PAD22-P)") (class "Default")
      (node (ref "PAD22") (pin "1") (pinfunction "P_1") (pintype "passive"))
      (node (ref "ZED1") (pin "197") (pinfunction "_P_197") (pintype "bidirectional"))
    )
    (net (code "25") (name "Net-(PAD25-P)") (class "Default")
      (node (ref "PAD25") (pin "1") (pinfunction "P_1") (pintype "passive"))
      (node (ref "ZED1") (pin "90") (pinfunction "_N_90") (pintype "bidirectional"))
    )
    (net (code "26") (name "Net-(PAD26-P)") (class "Default")
      (node (ref "PAD26") (pin "1") (pinfunction "P_1") (pintype "passive"))
      (node (ref "ZED1") (pin "88") (pinfunction "_P_88") (pintype "bidirectional"))
    )
    (net (code "27") (name "Net-(PAD27-P)") (class "Default")
      (node (ref "PAD27") (pin "1") (pinfunction "P_1") (pintype "passive"))
      (node (ref "ZED1") (pin "91") (pinfunction "_P_91") (pintype "bidirectional"))
    )
    (net (code "28") (name "Net-(PAD28-P)") (class "Default")
      (node (ref "PAD28") (pin "1") (pinfunction "P_1") (pintype "passive"))
      (node (ref "ZED1") (pin "93") (pinfunction "_N_93") (pintype "bidirectional"))
    )
    (net (code "29") (name "Net-(PAD31-P)") (class "Default")
      (node (ref "PAD31") (pin "1") (pinfunction "P_1") (pintype "passive"))
      (node (ref "ZED1") (pin "92") (pinfunction "_P_92") (pintype "bidirectional"))
    )
    (net (code "30") (name "Net-(PAD32-P)") (class "Default")
      (node (ref "PAD32") (pin "1") (pinfunction "P_1") (pintype "passive"))
      (node (ref "ZED1") (pin "94") (pinfunction "_N_94") (pintype "bidirectional"))
    )
    (net (code "31") (name "Net-(PAD33-P)") (class "Default")
      (node (ref "PAD33") (pin "1") (pinfunction "P_1") (pintype "passive"))
      (node (ref "ZED1") (pin "87") (pinfunction "_P_87") (pintype "bidirectional"))
    )
    (net (code "32") (name "Net-(PAD34-P)") (class "Default")
      (node (ref "PAD34") (pin "1") (pinfunction "P_1") (pintype "passive"))
      (node (ref "ZED1") (pin "89") (pinfunction "_N_89") (pintype "bidirectional"))
    )
    (net (code "33") (name "Net-(PAD37-P)") (class "Default")
      (node (ref "PAD37") (pin "1") (pinfunction "P_1") (pintype "passive"))
      (node (ref "ZED1") (pin "20") (pinfunction "_N_20") (pintype "bidirectional"))
    )
    (net (code "34") (name "Net-(PAD38-P)") (class "Default")
      (node (ref "PAD38") (pin "1") (pinfunction "P_1") (pintype "passive"))
      (node (ref "ZED1") (pin "18") (pinfunction "_P_18") (pintype "bidirectional"))
    )
    (net (code "35") (name "Net-(PAD39-P)") (class "Default")
      (node (ref "PAD39") (pin "1") (pinfunction "P_1") (pintype "passive"))
      (node (ref "ZED1") (pin "14") (pinfunction "_N_14") (pintype "bidirectional"))
    )
    (net (code "36") (name "Net-(PAD40-P)") (class "Default")
      (node (ref "PAD40") (pin "1") (pinfunction "P_1") (pintype "passive"))
      (node (ref "ZED1") (pin "12") (pinfunction "_P_12") (pintype "bidirectional"))
    )
    (net (code "37") (name "Net-(PAD43-P)") (class "Default")
      (node (ref "PAD43") (pin "1") (pinfunction "P_1") (pintype "passive"))
      (node (ref "ZED1") (pin "19") (pinfunction "_N_19") (pintype "bidirectional"))
    )
    (net (code "38") (name "Net-(PAD44-P)") (class "Default")
      (node (ref "PAD44") (pin "1") (pinfunction "P_1") (pintype "passive"))
      (node (ref "ZED1") (pin "17") (pinfunction "_P_17") (pintype "bidirectional"))
    )
    (net (code "39") (name "Net-(PAD45-P)") (class "Default")
      (node (ref "PAD45") (pin "1") (pinfunction "P_1") (pintype "passive"))
      (node (ref "ZED1") (pin "13") (pinfunction "_N_13") (pintype "bidirectional"))
    )
    (net (code "40") (name "Net-(PAD46-P)") (class "Default")
      (node (ref "PAD46") (pin "1") (pinfunction "P_1") (pintype "passive"))
      (node (ref "ZED1") (pin "11") (pinfunction "_P_11") (pintype "bidirectional"))
    )
    (net (code "41") (name "Net-(Q1-2)") (class "Default")
      (node (ref "C2") (pin "1") (pinfunction "1_1") (pintype "passive"))
      (node (ref "Q1") (pin "3") (pinfunction "2_3") (pintype "passive"))
      (node (ref "U1") (pin "2") (pinfunction "OSCO_2") (pintype "output"))
    )
    (net (code "42") (name "Net-(U1-DM)") (class "Default")
      (node (ref "U1") (pin "6") (pinfunction "DM_6") (pintype "bidirectional"))
      (node (ref "U3") (pin "2") (pinfunction "IO2_2") (pintype "bidirectional"))
      (node (ref "USB") (pin "D-") (pinfunction "D-_D-") (pintype "bidirectional"))
    )
    (net (code "43") (name "Net-(U1-DP)") (class "Default")
      (node (ref "U1") (pin "7") (pinfunction "DP_7") (pintype "bidirectional"))
      (node (ref "U3") (pin "1") (pinfunction "IO1_1") (pintype "bidirectional"))
      (node (ref "USB") (pin "D+") (pinfunction "D+_D+") (pintype "bidirectional"))
    )
    (net (code "44") (name "Net-(U1-EECLK)") (class "Default")
      (node (ref "R4") (pin "1") (pinfunction "1_1") (pintype "passive"))
      (node (ref "U1") (pin "44") (pinfunction "EECLK_44") (pintype "output"))
      (node (ref "U2") (pin "4") (pinfunction "CLK_4") (pintype "input"))
    )
    (net (code "45") (name "Net-(U1-EECS)") (class "Default")
      (node (ref "R3") (pin "1") (pinfunction "1_1") (pintype "passive"))
      (node (ref "U1") (pin "45") (pinfunction "EECS_45") (pintype "output"))
      (node (ref "U2") (pin "5") (pinfunction "CS_5") (pintype "input"))
    )
    (net (code "46") (name "Net-(U1-EEDATA)") (class "Default")
      (node (ref "R6") (pin "2") (pinfunction "2_2") (pintype "passive"))
      (node (ref "U1") (pin "43") (pinfunction "EEDATA_43") (pintype "bidirectional"))
      (node (ref "U2") (pin "3") (pinfunction "DI_3") (pintype "input"))
    )
    (net (code "47") (name "Net-(U1-OSCI)") (class "Default")
      (node (ref "C1") (pin "1") (pinfunction "1_1") (pintype "passive"))
      (node (ref "Q1") (pin "1") (pinfunction "1_1") (pintype "passive"))
      (node (ref "U1") (pin "1") (pinfunction "OSCI_1") (pintype "input"))
    )
    (net (code "48") (name "Net-(U1-REF)") (class "Default")
      (node (ref "R1") (pin "2") (pinfunction "2_2") (pintype "passive"))
      (node (ref "U1") (pin "5") (pinfunction "REF_5") (pintype "input"))
    )
    (net (code "49") (name "Net-(U1-RESET#)") (class "Default")
      (node (ref "C3") (pin "1") (pinfunction "1_1") (pintype "passive"))
      (node (ref "R2") (pin "1") (pinfunction "1_1") (pintype "passive"))
      (node (ref "U1") (pin "34") (pinfunction "RESET#_34") (pintype "input"))
    )
    (net (code "50") (name "Net-(U2-DO)") (class "Default")
      (node (ref "R5") (pin "1") (pinfunction "1_1") (pintype "passive"))
      (node (ref "R6") (pin "1") (pinfunction "1_1") (pintype "passive"))
      (node (ref "U2") (pin "1") (pinfunction "DO_1") (pintype "output"))
    )
    (net (code "51") (name "Net-(U3-IO3)") (class "Default")
      (node (ref "U3") (pin "4") (pinfunction "IO3_4") (pintype "bidirectional"))
      (node (ref "USB") (pin "ID") (pinfunction "USBID_ID") (pintype "bidirectional"))
    )
    (net (code "52") (name "Net-(X1-A)") (class "Default")
      (node (ref "X1") (pin "2") (pinfunction "A_2") (pintype "bidirectional"))
      (node (ref "ZED1") (pin "29") (pinfunction "_P_29") (pintype "bidirectional"))
    )
    (net (code "53") (name "Net-(X1-B)") (class "Default")
      (node (ref "X1") (pin "6") (pinfunction "B_6") (pintype "bidirectional"))
      (node (ref "ZED1") (pin "23") (pinfunction "_P_23") (pintype "bidirectional"))
    )
    (net (code "54") (name "Net-(X1-~{A})") (class "Default")
      (node (ref "X1") (pin "3") (pinfunction "~{A}_3") (pintype "bidirectional"))
      (node (ref "ZED1") (pin "31") (pinfunction "_N_31") (pintype "bidirectional"))
    )
    (net (code "55") (name "Net-(X1-~{B})") (class "Default")
      (node (ref "X1") (pin "5") (pinfunction "~{B}_5") (pintype "bidirectional"))
      (node (ref "ZED1") (pin "25") (pinfunction "_N_25") (pintype "bidirectional"))
    )
    (net (code "56") (name "Net-(X2-A)") (class "Default")
      (node (ref "X2") (pin "2") (pinfunction "A_2") (pintype "bidirectional"))
      (node (ref "ZED1") (pin "30") (pinfunction "_P_30") (pintype "bidirectional"))
    )
    (net (code "57") (name "Net-(X2-B)") (class "Default")
      (node (ref "X2") (pin "6") (pinfunction "B_6") (pintype "bidirectional"))
      (node (ref "ZED1") (pin "36") (pinfunction "_P_36") (pintype "bidirectional"))
    )
    (net (code "58") (name "Net-(X2-~{A})") (class "Default")
      (node (ref "X2") (pin "3") (pinfunction "~{A}_3") (pintype "bidirectional"))
      (node (ref "ZED1") (pin "32") (pinfunction "_N_32") (pintype "bidirectional"))
    )
    (net (code "59") (name "Net-(X2-~{B})") (class "Default")
      (node (ref "X2") (pin "5") (pinfunction "~{B}_5") (pintype "bidirectional"))
      (node (ref "ZED1") (pin "38") (pinfunction "_N_38") (pintype "bidirectional"))
    )
    (net (code "60") (name "Net-(X3-A)") (class "Default")
      (node (ref "X3") (pin "2") (pinfunction "A_2") (pintype "bidirectional"))
      (node (ref "ZED1") (pin "135") (pinfunction "_P_135") (pintype "bidirectional"))
    )
    (net (code "61") (name "Net-(X3-B)") (class "Default")
      (node (ref "X3") (pin "6") (pinfunction "B_6") (pintype "bidirectional"))
      (node (ref "ZED1") (pin "129") (pinfunction "_P_129") (pintype "bidirectional"))
    )
    (net (code "62") (name "Net-(X3-~{A})") (class "Default")
      (node (ref "X3") (pin "3") (pinfunction "~{A}_3") (pintype "bidirectional"))
      (node (ref "ZED1") (pin "137") (pinfunction "_N_137") (pintype "bidirectional"))
    )
    (net (code "63") (name "Net-(X3-~{B})") (class "Default")
      (node (ref "X3") (pin "5") (pinfunction "~{B}_5") (pintype "bidirectional"))
      (node (ref "ZED1") (pin "131") (pinfunction "_N_131") (pintype "bidirectional"))
    )
    (net (code "64") (name "Net-(X4-A)") (class "Default")
      (node (ref "X4") (pin "2") (pinfunction "A_2") (pintype "bidirectional"))
      (node (ref "ZED1") (pin "130") (pinfunction "_P_130") (pintype "bidirectional"))
    )
    (net (code "65") (name "Net-(X4-B)") (class "Default")
      (node (ref "X4") (pin "6") (pinfunction "B_6") (pintype "bidirectional"))
      (node (ref "ZED1") (pin "136") (pinfunction "_P_136") (pintype "bidirectional"))
    )
    (net (code "66") (name "Net-(X4-~{A})") (class "Default")
      (node (ref "X4") (pin "3") (pinfunction "~{A}_3") (pintype "bidirectional"))
      (node (ref "ZED1") (pin "132") (pinfunction "_N_132") (pintype "bidirectional"))
    )
    (net (code "67") (name "Net-(X4-~{B})") (class "Default")
      (node (ref "X4") (pin "5") (pinfunction "~{B}_5") (pintype "bidirectional"))
      (node (ref "ZED1") (pin "138") (pinfunction "_N_138") (pintype "bidirectional"))
    )
    (net (code "68") (name "Net-(X5-A)") (class "Default")
      (node (ref "X5") (pin "2") (pinfunction "A_2") (pintype "bidirectional"))
      (node (ref "ZED1") (pin "41") (pinfunction "_P_41") (pintype "bidirectional"))
    )
    (net (code "69") (name "Net-(X5-B)") (class "Default")
      (node (ref "X5") (pin "6") (pinfunction "B_6") (pintype "bidirectional"))
      (node (ref "ZED1") (pin "47") (pinfunction "_P_47") (pintype "bidirectional"))
    )
    (net (code "70") (name "Net-(X5-~{A})") (class "Default")
      (node (ref "X5") (pin "3") (pinfunction "~{A}_3") (pintype "bidirectional"))
      (node (ref "ZED1") (pin "43") (pinfunction "_N_43") (pintype "bidirectional"))
    )
    (net (code "71") (name "Net-(X5-~{B})") (class "Default")
      (node (ref "X5") (pin "5") (pinfunction "~{B}_5") (pintype "bidirectional"))
      (node (ref "ZED1") (pin "49") (pinfunction "_N_49") (pintype "bidirectional"))
    )
    (net (code "72") (name "Net-(X6-A)") (class "Default")
      (node (ref "X6") (pin "2") (pinfunction "A_2") (pintype "bidirectional"))
      (node (ref "ZED1") (pin "42") (pinfunction "_P_42") (pintype "bidirectional"))
    )
    (net (code "73") (name "Net-(X6-B)") (class "Default")
      (node (ref "X6") (pin "6") (pinfunction "B_6") (pintype "bidirectional"))
      (node (ref "ZED1") (pin "48") (pinfunction "_P_48") (pintype "bidirectional"))
    )
    (net (code "74") (name "Net-(X6-~{A})") (class "Default")
      (node (ref "X6") (pin "3") (pinfunction "~{A}_3") (pintype "bidirectional"))
      (node (ref "ZED1") (pin "44") (pinfunction "_N_44") (pintype "bidirectional"))
    )
    (net (code "75") (name "Net-(X6-~{B})") (class "Default")
      (node (ref "X6") (pin "5") (pinfunction "~{B}_5") (pintype "bidirectional"))
      (node (ref "ZED1") (pin "50") (pinfunction "_N_50") (pintype "bidirectional"))
    )
    (net (code "76") (name "Net-(X7-A)") (class "Default")
      (node (ref "X7") (pin "2") (pinfunction "A_2") (pintype "bidirectional"))
      (node (ref "ZED1") (pin "153") (pinfunction "_P_153") (pintype "bidirectional"))
    )
    (net (code "77") (name "Net-(X7-B)") (class "Default")
      (node (ref "X7") (pin "6") (pinfunction "B_6") (pintype "bidirectional"))
      (node (ref "ZED1") (pin "147") (pinfunction "_P_147") (pintype "bidirectional"))
    )
    (net (code "78") (name "Net-(X7-~{A})") (class "Default")
      (node (ref "X7") (pin "3") (pinfunction "~{A}_3") (pintype "bidirectional"))
      (node (ref "ZED1") (pin "155") (pinfunction "_N_155") (pintype "bidirectional"))
    )
    (net (code "79") (name "Net-(X7-~{B})") (class "Default")
      (node (ref "X7") (pin "5") (pinfunction "~{B}_5") (pintype "bidirectional"))
      (node (ref "ZED1") (pin "149") (pinfunction "_N_149") (pintype "bidirectional"))
    )
    (net (code "80") (name "Net-(X8-A)") (class "Default")
      (node (ref "X8") (pin "2") (pinfunction "A_2") (pintype "bidirectional"))
      (node (ref "ZED1") (pin "154") (pinfunction "_P_154") (pintype "bidirectional"))
    )
    (net (code "81") (name "Net-(X8-B)") (class "Default")
      (node (ref "X8") (pin "6") (pinfunction "B_6") (pintype "bidirectional"))
      (node (ref "ZED1") (pin "148") (pinfunction "_P_148") (pintype "bidirectional"))
    )
    (net (code "82") (name "Net-(X8-~{A})") (class "Default")
      (node (ref "X8") (pin "3") (pinfunction "~{A}_3") (pintype "bidirectional"))
      (node (ref "ZED1") (pin "156") (pinfunction "_N_156") (pintype "bidirectional"))
    )
    (net (code "83") (name "Net-(X8-~{B})") (class "Default")
      (node (ref "X8") (pin "5") (pinfunction "~{B}_5") (pintype "bidirectional"))
      (node (ref "ZED1") (pin "150") (pinfunction "_N_150") (pintype "bidirectional"))
    )
    (net (code "84") (name "Net-(X9-A)") (class "Default")
      (node (ref "X9") (pin "2") (pinfunction "A_2") (pintype "bidirectional"))
      (node (ref "ZED1") (pin "168") (pinfunction "_P_168") (pintype "bidirectional"))
    )
    (net (code "85") (name "Net-(X9-B)") (class "Default")
      (node (ref "X9") (pin "6") (pinfunction "B_6") (pintype "bidirectional"))
      (node (ref "ZED1") (pin "174") (pinfunction "_P_174") (pintype "bidirectional"))
    )
    (net (code "86") (name "Net-(X9-~{A})") (class "Default")
      (node (ref "X9") (pin "3") (pinfunction "~{A}_3") (pintype "bidirectional"))
      (node (ref "ZED1") (pin "170") (pinfunction "_N_170") (pintype "bidirectional"))
    )
    (net (code "87") (name "Net-(X9-~{B})") (class "Default")
      (node (ref "X9") (pin "5") (pinfunction "~{B}_5") (pintype "bidirectional"))
      (node (ref "ZED1") (pin "176") (pinfunction "_N_176") (pintype "bidirectional"))
    )
    (net (code "88") (name "Net-(X10-A)") (class "Default")
      (node (ref "X10") (pin "2") (pinfunction "A_2") (pintype "bidirectional"))
      (node (ref "ZED1") (pin "173") (pinfunction "_P_173") (pintype "bidirectional"))
    )
    (net (code "89") (name "Net-(X10-B)") (class "Default")
      (node (ref "X10") (pin "6") (pinfunction "B_6") (pintype "bidirectional"))
      (node (ref "ZED1") (pin "167") (pinfunction "_P_167") (pintype "bidirectional"))
    )
    (net (code "90") (name "Net-(X10-~{A})") (class "Default")
      (node (ref "X10") (pin "3") (pinfunction "~{A}_3") (pintype "bidirectional"))
      (node (ref "ZED1") (pin "175") (pinfunction "_N_175") (pintype "bidirectional"))
    )
    (net (code "91") (name "Net-(X10-~{B})") (class "Default")
      (node (ref "X10") (pin "5") (pinfunction "~{B}_5") (pintype "bidirectional"))
      (node (ref "ZED1") (pin "169") (pinfunction "_N_169") (pintype "bidirectional"))
    )
    (net (code "92") (name "Net-(X11-A)") (class "Default")
      (node (ref "X11") (pin "2") (pinfunction "A_2") (pintype "bidirectional"))
      (node (ref "ZED1") (pin "67") (pinfunction "_P_67") (pintype "bidirectional"))
    )
    (net (code "93") (name "Net-(X11-B)") (class "Default")
      (node (ref "X11") (pin "6") (pinfunction "B_6") (pintype "bidirectional"))
      (node (ref "ZED1") (pin "61") (pinfunction "_P_61") (pintype "bidirectional"))
    )
    (net (code "94") (name "Net-(X11-~{A})") (class "Default")
      (node (ref "X11") (pin "3") (pinfunction "~{A}_3") (pintype "bidirectional"))
      (node (ref "ZED1") (pin "69") (pinfunction "_N_69") (pintype "bidirectional"))
    )
    (net (code "95") (name "Net-(X11-~{B})") (class "Default")
      (node (ref "X11") (pin "5") (pinfunction "~{B}_5") (pintype "bidirectional"))
      (node (ref "ZED1") (pin "63") (pinfunction "_N_63") (pintype "bidirectional"))
    )
    (net (code "96") (name "Net-(X12-A)") (class "Default")
      (node (ref "X12") (pin "2") (pinfunction "A_2") (pintype "bidirectional"))
      (node (ref "ZED1") (pin "62") (pinfunction "_P_62") (pintype "bidirectional"))
    )
    (net (code "97") (name "Net-(X12-B)") (class "Default")
      (node (ref "X12") (pin "6") (pinfunction "B_6") (pintype "bidirectional"))
      (node (ref "ZED1") (pin "68") (pinfunction "_P_68") (pintype "bidirectional"))
    )
    (net (code "98") (name "Net-(X12-~{A})") (class "Default")
      (node (ref "X12") (pin "3") (pinfunction "~{A}_3") (pintype "bidirectional"))
      (node (ref "ZED1") (pin "64") (pinfunction "_N_64") (pintype "bidirectional"))
    )
    (net (code "99") (name "Net-(X12-~{B})") (class "Default")
      (node (ref "X12") (pin "5") (pinfunction "~{B}_5") (pintype "bidirectional"))
      (node (ref "ZED1") (pin "70") (pinfunction "_N_70") (pintype "bidirectional"))
    )
    (net (code "100") (name "Net-(ZED1AG-_N)") (class "Default")
      (node (ref "Y4") (pin "1") (pinfunction "1_1") (pintype "passive"))
      (node (ref "ZED1") (pin "84") (pinfunction "_N_84") (pintype "bidirectional"))
    )
    (net (code "101") (name "Net-(ZED1AG-_P)") (class "Default")
      (node (ref "Y3") (pin "1") (pinfunction "1_1") (pintype "passive"))
      (node (ref "ZED1") (pin "82") (pinfunction "_P_82") (pintype "bidirectional"))
    )
    (net (code "102") (name "Net-(ZED1AK-_N)") (class "Default")
      (node (ref "Y6") (pin "1") (pinfunction "1_1") (pintype "passive"))
      (node (ref "ZED1") (pin "125") (pinfunction "_N_125") (pintype "bidirectional"))
    )
    (net (code "103") (name "Net-(ZED1AK-_P)") (class "Default")
      (node (ref "Y5") (pin "1") (pinfunction "1_1") (pintype "passive"))
      (node (ref "ZED1") (pin "123") (pinfunction "_P_123") (pintype "bidirectional"))
    )
    (net (code "104") (name "Net-(ZED1AR-_N)") (class "Default")
      (node (ref "Z6") (pin "1") (pinfunction "1_1") (pintype "passive"))
      (node (ref "ZED1") (pin "144") (pinfunction "_N_144") (pintype "bidirectional"))
    )
    (net (code "105") (name "Net-(ZED1AR-_P)") (class "Default")
      (node (ref "Z5") (pin "1") (pinfunction "1_1") (pintype "passive"))
      (node (ref "ZED1") (pin "142") (pinfunction "_P_142") (pintype "bidirectional"))
    )
    (net (code "106") (name "Net-(ZED1AX-_N)") (class "Default")
      (node (ref "Z1") (pin "1") (pinfunction "1_1") (pintype "passive"))
      (node (ref "ZED1") (pin "164") (pinfunction "_N_164") (pintype "bidirectional"))
    )
    (net (code "107") (name "Net-(ZED1AX-_P)") (class "Default")
      (node (ref "Z2") (pin "1") (pinfunction "1_1") (pintype "passive"))
      (node (ref "ZED1") (pin "162") (pinfunction "_P_162") (pintype "bidirectional"))
    )
    (net (code "108") (name "Net-(ZED1BC-_N)") (class "Default")
      (node (ref "Y1") (pin "1") (pinfunction "1_1") (pintype "passive"))
      (node (ref "ZED1") (pin "183") (pinfunction "_N_183") (pintype "bidirectional"))
    )
    (net (code "109") (name "Net-(ZED1BC-_P)") (class "Default")
      (node (ref "Y2") (pin "1") (pinfunction "1_1") (pintype "passive"))
      (node (ref "ZED1") (pin "181") (pinfunction "_P_181") (pintype "bidirectional"))
    )
    (net (code "110") (name "Net-(ZED1X-_N)") (class "Default")
      (node (ref "Z4") (pin "1") (pinfunction "1_1") (pintype "passive"))
      (node (ref "ZED1") (pin "55") (pinfunction "_N_55") (pintype "bidirectional"))
    )
    (net (code "111") (name "Net-(ZED1X-_P)") (class "Default")
      (node (ref "Z3") (pin "1") (pinfunction "1_1") (pintype "passive"))
      (node (ref "ZED1") (pin "53") (pinfunction "_P_53") (pintype "bidirectional"))
    )
    (net (code "112") (name "PMOD_A_VCC") (class "Default")
      (node (ref "JP1") (pin "1") (pinfunction "1_1") (pintype "passive"))
      (node (ref "PAD12") (pin "1") (pinfunction "P_1") (pintype "passive"))
      (node (ref "PAD6") (pin "1") (pinfunction "P_1") (pintype "passive"))
    )
    (net (code "113") (name "PMOD_B_VCC") (class "Default")
      (node (ref "JP2") (pin "1") (pinfunction "1_1") (pintype "passive"))
      (node (ref "PAD18") (pin "1") (pinfunction "P_1") (pintype "passive"))
      (node (ref "PAD24") (pin "1") (pinfunction "P_1") (pintype "passive"))
    )
    (net (code "114") (name "PMOD_C_VCC") (class "Default")
      (node (ref "JP3") (pin "2") (pinfunction "2_2") (pintype "passive"))
      (node (ref "PAD30") (pin "1") (pinfunction "P_1") (pintype "passive"))
      (node (ref "PAD36") (pin "1") (pinfunction "P_1") (pintype "passive"))
    )
    (net (code "115") (name "PMOD_D_VCC") (class "Default")
      (node (ref "JP4") (pin "2") (pinfunction "2_2") (pintype "passive"))
      (node (ref "PAD42") (pin "1") (pinfunction "P_1") (pintype "passive"))
      (node (ref "PAD48") (pin "1") (pinfunction "P_1") (pintype "passive"))
    )
    (net (code "116") (name "VCCA") (class "Default")
      (node (ref "C6") (pin "1") (pinfunction "1_1") (pintype "passive"))
      (node (ref "U1") (pin "37") (pinfunction "VCCA_37") (pintype "output"))
    )
    (net (code "117") (name "VCCD") (class "Default")
      (node (ref "FB2") (pin "1") (pinfunction "P$1_1") (pintype "passive"))
      (node (ref "FB3") (pin "1") (pinfunction "P$1_1") (pintype "passive"))
      (node (ref "R2") (pin "2") (pinfunction "2_2") (pintype "passive"))
      (node (ref "R3") (pin "2") (pinfunction "2_2") (pintype "passive"))
      (node (ref "R4") (pin "2") (pinfunction "2_2") (pintype "passive"))
      (node (ref "R5") (pin "2") (pinfunction "2_2") (pintype "passive"))
      (node (ref "U1") (pin "12") (pinfunction "VCCIO_12") (pintype "power_in"))
      (node (ref "U1") (pin "24") (pinfunction "VCCIO_24") (pintype "power_in"))
      (node (ref "U1") (pin "39") (pinfunction "VCCD_39") (pintype "power_in"))
      (node (ref "U1") (pin "46") (pinfunction "VCCIO_46") (pintype "power_in"))
      (node (ref "U2") (pin "6") (pinfunction "VCC_6") (pintype "power_in"))
    )
    (net (code "118") (name "VCCO_13") (class "Default")
      (node (ref "JP2") (pin "2") (pinfunction "2_2") (pintype "passive"))
      (node (ref "ZED1") (pin "198") (pinfunction "VCCO_13_198") (pintype "power_in"))
    )
    (net (code "119") (name "VCCO_34") (class "Default")
      (node (ref "JP3") (pin "1") (pinfunction "1_1") (pintype "passive"))
      (node (ref "ZED1") (pin "78") (pinfunction "VCCO_34_78") (pintype "power_in"))
      (node (ref "ZED1") (pin "79") (pinfunction "VCCO_34_79") (pintype "power_in"))
      (node (ref "ZED1") (pin "80") (pinfunction "VCCO_34_80") (pintype "power_in"))
    )
    (net (code "120") (name "VCCO_35") (class "Default")
      (node (ref "JP2") (pin "3") (pinfunction "3_3") (pintype "passive"))
      (node (ref "ZED1") (pin "178") (pinfunction "VCCO_35_178") (pintype "power_in"))
      (node (ref "ZED1") (pin "179") (pinfunction "VCCO_35_179") (pintype "power_in"))
      (node (ref "ZED1") (pin "180") (pinfunction "VCCO_35_180") (pintype "power_in"))
    )
    (net (code "121") (name "VCORE") (class "Default")
      (node (ref "C5") (pin "1") (pinfunction "1_1") (pintype "passive"))
      (node (ref "U1") (pin "38") (pinfunction "VCORE_38") (pintype "output"))
    )
    (net (code "122") (name "VIN_HDR") (class "Default")
      (node (ref "JP1") (pin "2") (pinfunction "2_2") (pintype "passive"))
      (node (ref "JP4") (pin "1") (pinfunction "1_1") (pintype "passive"))
      (node (ref "ZED1") (pin "112") (pinfunction "VIN_HDR_112") (pintype "power_in"))
      (node (ref "ZED1") (pin "157") (pinfunction "VIN_HDR_157") (pintype "power_in"))
      (node (ref "ZED1") (pin "158") (pinfunction "VIN_HDR_158") (pintype "power_in"))
      (node (ref "ZED1") (pin "159") (pinfunction "VIN_HDR_159") (pintype "power_in"))
      (node (ref "ZED1") (pin "160") (pinfunction "VIN_HDR_160") (pintype "power_in"))
      (node (ref "ZED1") (pin "57") (pinfunction "VIN_HDR_57") (pintype "power_in"))
      (node (ref "ZED1") (pin "58") (pinfunction "VIN_HDR_58") (pintype "power_in"))
      (node (ref "ZED1") (pin "59") (pinfunction "VIN_HDR_59") (pintype "power_in"))
      (node (ref "ZED1") (pin "60") (pinfunction "VIN_HDR_60") (pintype "power_in"))
    )
    (net (code "123") (name "VPHY") (class "Default")
      (node (ref "C7") (pin "1") (pinfunction "1_1") (pintype "passive"))
      (node (ref "C8") (pin "1") (pinfunction "1_1") (pintype "passive"))
      (node (ref "FB2") (pin "2") (pinfunction "P$2_2") (pintype "passive"))
      (node (ref "U1") (pin "3") (pinfunction "VPHY_3") (pintype "power_in"))
    )
    (net (code "124") (name "VPLL") (class "Default")
      (node (ref "C10") (pin "1") (pinfunction "1_1") (pintype "passive"))
      (node (ref "C9") (pin "1") (pinfunction "1_1") (pintype "passive"))
      (node (ref "FB3") (pin "2") (pinfunction "P$2_2") (pintype "passive"))
      (node (ref "U1") (pin "8") (pinfunction "VPLL_8") (pintype "power_in"))
    )
    (net (code "125") (name "unconnected-(U1-ACBUS0-Pad21)") (class "Default")
      (node (ref "U1") (pin "21") (pinfunction "ACBUS0_21") (pintype "bidirectional"))
    )
    (net (code "126") (name "unconnected-(U1-ACBUS1-Pad25)") (class "Default")
      (node (ref "U1") (pin "25") (pinfunction "ACBUS1_25") (pintype "bidirectional"))
    )
    (net (code "127") (name "unconnected-(U1-ACBUS2-Pad26)") (class "Default")
      (node (ref "U1") (pin "26") (pinfunction "ACBUS2_26") (pintype "bidirectional"))
    )
    (net (code "128") (name "unconnected-(U1-ACBUS3-Pad27)") (class "Default")
      (node (ref "U1") (pin "27") (pinfunction "ACBUS3_27") (pintype "bidirectional"))
    )
    (net (code "129") (name "unconnected-(U1-ACBUS4-Pad28)") (class "Default")
      (node (ref "U1") (pin "28") (pinfunction "ACBUS4_28") (pintype "bidirectional"))
    )
    (net (code "130") (name "unconnected-(U1-ACBUS5-Pad29)") (class "Default")
      (node (ref "U1") (pin "29") (pinfunction "ACBUS5_29") (pintype "bidirectional"))
    )
    (net (code "131") (name "unconnected-(U1-ACBUS6-Pad30)") (class "Default")
      (node (ref "U1") (pin "30") (pinfunction "ACBUS6_30") (pintype "bidirectional"))
    )
    (net (code "132") (name "unconnected-(U1-ACBUS7-Pad31)") (class "Default")
      (node (ref "U1") (pin "31") (pinfunction "ACBUS7_31") (pintype "bidirectional"))
    )
    (net (code "133") (name "unconnected-(U1-ACBUS8-Pad32)") (class "Default")
      (node (ref "U1") (pin "32") (pinfunction "ACBUS8_32") (pintype "bidirectional"))
    )
    (net (code "134") (name "unconnected-(U1-ACBUS9-Pad33)") (class "Default")
      (node (ref "U1") (pin "33") (pinfunction "ACBUS9_33") (pintype "bidirectional"))
    )
    (net (code "135") (name "unconnected-(U1-ADBUS4-Pad17)") (class "Default")
      (node (ref "U1") (pin "17") (pinfunction "ADBUS4_17") (pintype "output"))
    )
    (net (code "136") (name "unconnected-(U1-ADBUS5-Pad18)") (class "Default")
      (node (ref "U1") (pin "18") (pinfunction "ADBUS5_18") (pintype "input"))
    )
    (net (code "137") (name "unconnected-(U1-ADBUS6-Pad19)") (class "Default")
      (node (ref "U1") (pin "19") (pinfunction "ADBUS6_19") (pintype "input"))
    )
    (net (code "138") (name "unconnected-(U1-ADBUS7-Pad20)") (class "Default")
      (node (ref "U1") (pin "20") (pinfunction "ADBUS7_20") (pintype "input"))
    )
    (net (code "139") (name "unconnected-(U1-TEST-Pad42)") (class "Default")
      (node (ref "U1") (pin "42") (pinfunction "TEST_42") (pintype "input"))
    )
    (net (code "140") (name "unconnected-(ZED1AD-_N-Pad75)") (class "Default")
      (node (ref "ZED1") (pin "75") (pinfunction "_N_75") (pintype "bidirectional"))
    )
    (net (code "141") (name "unconnected-(ZED1AD-_P-Pad73)") (class "Default")
      (node (ref "ZED1") (pin "73") (pinfunction "_P_73") (pintype "bidirectional"))
    )
    (net (code "142") (name "unconnected-(ZED1AE-_N-Pad76)") (class "Default")
      (node (ref "ZED1") (pin "76") (pinfunction "_N_76") (pintype "bidirectional"))
    )
    (net (code "143") (name "unconnected-(ZED1AE-_P-Pad74)") (class "Default")
      (node (ref "ZED1") (pin "74") (pinfunction "_P_74") (pintype "bidirectional"))
    )
    (net (code "144") (name "unconnected-(ZED1AF-_N-Pad83)") (class "Default")
      (node (ref "ZED1") (pin "83") (pinfunction "_N_83") (pintype "bidirectional"))
    )
    (net (code "145") (name "unconnected-(ZED1AF-_P-Pad81)") (class "Default")
      (node (ref "ZED1") (pin "81") (pinfunction "_P_81") (pintype "bidirectional"))
    )
    (net (code "146") (name "unconnected-(ZED1AH-_0-Pad9)") (class "Default")
      (node (ref "ZED1") (pin "9") (pinfunction "_0_9") (pintype "bidirectional"))
    )
    (net (code "147") (name "unconnected-(ZED1AH-_1-Pad10)") (class "Default")
      (node (ref "ZED1") (pin "10") (pinfunction "_1_10") (pintype "bidirectional"))
    )
    (net (code "148") (name "unconnected-(ZED1AW-_N-Pad163)") (class "Default")
      (node (ref "ZED1") (pin "163") (pinfunction "_N_163") (pintype "bidirectional"))
    )
    (net (code "149") (name "unconnected-(ZED1AW-_P-Pad161)") (class "Default")
      (node (ref "ZED1") (pin "161") (pinfunction "_P_161") (pintype "bidirectional"))
    )
    (net (code "150") (name "unconnected-(ZED1BE-_N-Pad189)") (class "Default")
      (node (ref "ZED1") (pin "189") (pinfunction "_N_189") (pintype "bidirectional"))
    )
    (net (code "151") (name "unconnected-(ZED1BE-_P-Pad187)") (class "Default")
      (node (ref "ZED1") (pin "187") (pinfunction "_P_187") (pintype "bidirectional"))
    )
    (net (code "152") (name "unconnected-(ZED1BG-_0-Pad113)") (class "Default")
      (node (ref "ZED1") (pin "113") (pinfunction "_0_113") (pintype "bidirectional"))
    )
    (net (code "153") (name "unconnected-(ZED1BG-_1-Pad114)") (class "Default")
      (node (ref "ZED1") (pin "114") (pinfunction "_1_114") (pintype "bidirectional"))
    )
    (net (code "154") (name "unconnected-(ZED1BH-_N-Pad99)") (class "Default")
      (node (ref "ZED1") (pin "99") (pinfunction "_N_99") (pintype "bidirectional"))
    )
    (net (code "155") (name "unconnected-(ZED1BH-_P-Pad97)") (class "Default")
      (node (ref "ZED1") (pin "97") (pinfunction "_P_97") (pintype "bidirectional"))
    )
    (net (code "156") (name "unconnected-(ZED1BI-FPGA_DONE-Pad8)") (class "Default")
      (node (ref "ZED1") (pin "8") (pinfunction "FPGA_DONE_8") (pintype "output"))
    )
    (net (code "157") (name "unconnected-(ZED1BI-PG_MODULE-Pad111)") (class "Default")
      (node (ref "ZED1") (pin "111") (pinfunction "PG_MODULE_111") (pintype "output"))
    )
    (net (code "158") (name "unconnected-(ZED1BI-PWR_ENABLE-Pad5)") (class "Default")
      (node (ref "ZED1") (pin "5") (pinfunction "PWR_ENABLE_5") (pintype "input"))
    )
    (net (code "159") (name "unconnected-(ZED1BI-~{CARRIER_SRST}-Pad6)") (class "Default")
      (node (ref "ZED1") (pin "6") (pinfunction "~{CARRIER_SRST}_6") (pintype "output"))
    )
    (net (code "160") (name "unconnected-(ZED1BI-~{INIT}-Pad109)") (class "Default")
      (node (ref "ZED1") (pin "109") (pinfunction "~{INIT}_109") (pintype "input"))
    )
    (net (code "161") (name "unconnected-(ZED1BI-~{PROGRAM}-Pad110)") (class "Default")
      (node (ref "ZED1") (pin "110") (pinfunction "~{PROGRAM}_110") (pintype "input"))
    )
    (net (code "162") (name "unconnected-(ZED1F-_N-Pad196)") (class "Default")
      (node (ref "ZED1") (pin "196") (pinfunction "_N_196") (pintype "bidirectional"))
    )
    (net (code "163") (name "unconnected-(ZED1F-_P-Pad194)") (class "Default")
      (node (ref "ZED1") (pin "194") (pinfunction "_P_194") (pintype "bidirectional"))
    )
    (net (code "164") (name "unconnected-(ZED1H-_0-Pad200)") (class "Default")
      (node (ref "ZED1") (pin "200") (pinfunction "_0_200") (pintype "bidirectional"))
    )
    (net (code "165") (name "unconnected-(ZED1I-_N-Pad100)") (class "Default")
      (node (ref "ZED1") (pin "100") (pinfunction "_N_100") (pintype "bidirectional"))
    )
    (net (code "166") (name "unconnected-(ZED1I-_P-Pad98)") (class "Default")
      (node (ref "ZED1") (pin "98") (pinfunction "_P_98") (pintype "bidirectional"))
    )
    (net (code "167") (name "unconnected-(ZED1O-_N-Pad26)") (class "Default")
      (node (ref "ZED1") (pin "26") (pinfunction "_N_26") (pintype "bidirectional"))
    )
    (net (code "168") (name "unconnected-(ZED1O-_P-Pad24)") (class "Default")
      (node (ref "ZED1") (pin "24") (pinfunction "_P_24") (pintype "bidirectional"))
    )
    (net (code "169") (name "unconnected-(ZED1R-_N-Pad37)") (class "Default")
      (node (ref "ZED1") (pin "37") (pinfunction "_N_37") (pintype "bidirectional"))
    )
    (net (code "170") (name "unconnected-(ZED1R-_P-Pad35)") (class "Default")
      (node (ref "ZED1") (pin "35") (pinfunction "_P_35") (pintype "bidirectional"))
    )
    (net (code "171") (name "unconnected-(ZED1Y-_N-Pad56)") (class "Default")
      (node (ref "ZED1") (pin "56") (pinfunction "_N_56") (pintype "bidirectional"))
    )
    (net (code "172") (name "unconnected-(ZED1Y-_P-Pad54)") (class "Default")
      (node (ref "ZED1") (pin "54") (pinfunction "_P_54") (pintype "bidirectional"))
    )
  )
)
